# CX3_Camera.net
KiCad netlist of a schematic drawn in Altium Designer
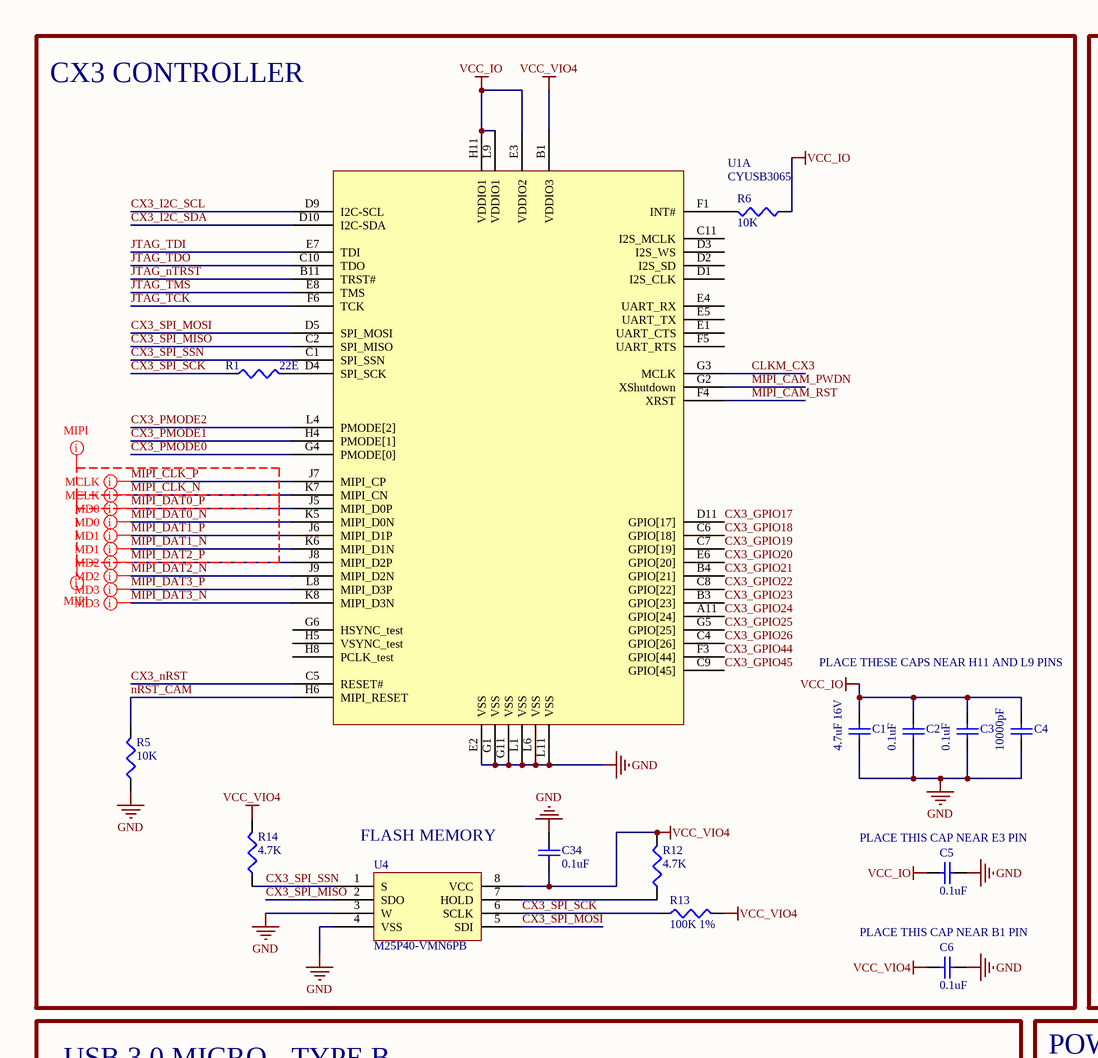
[diagram p0: CX3_Camera.SchDoc, top left]
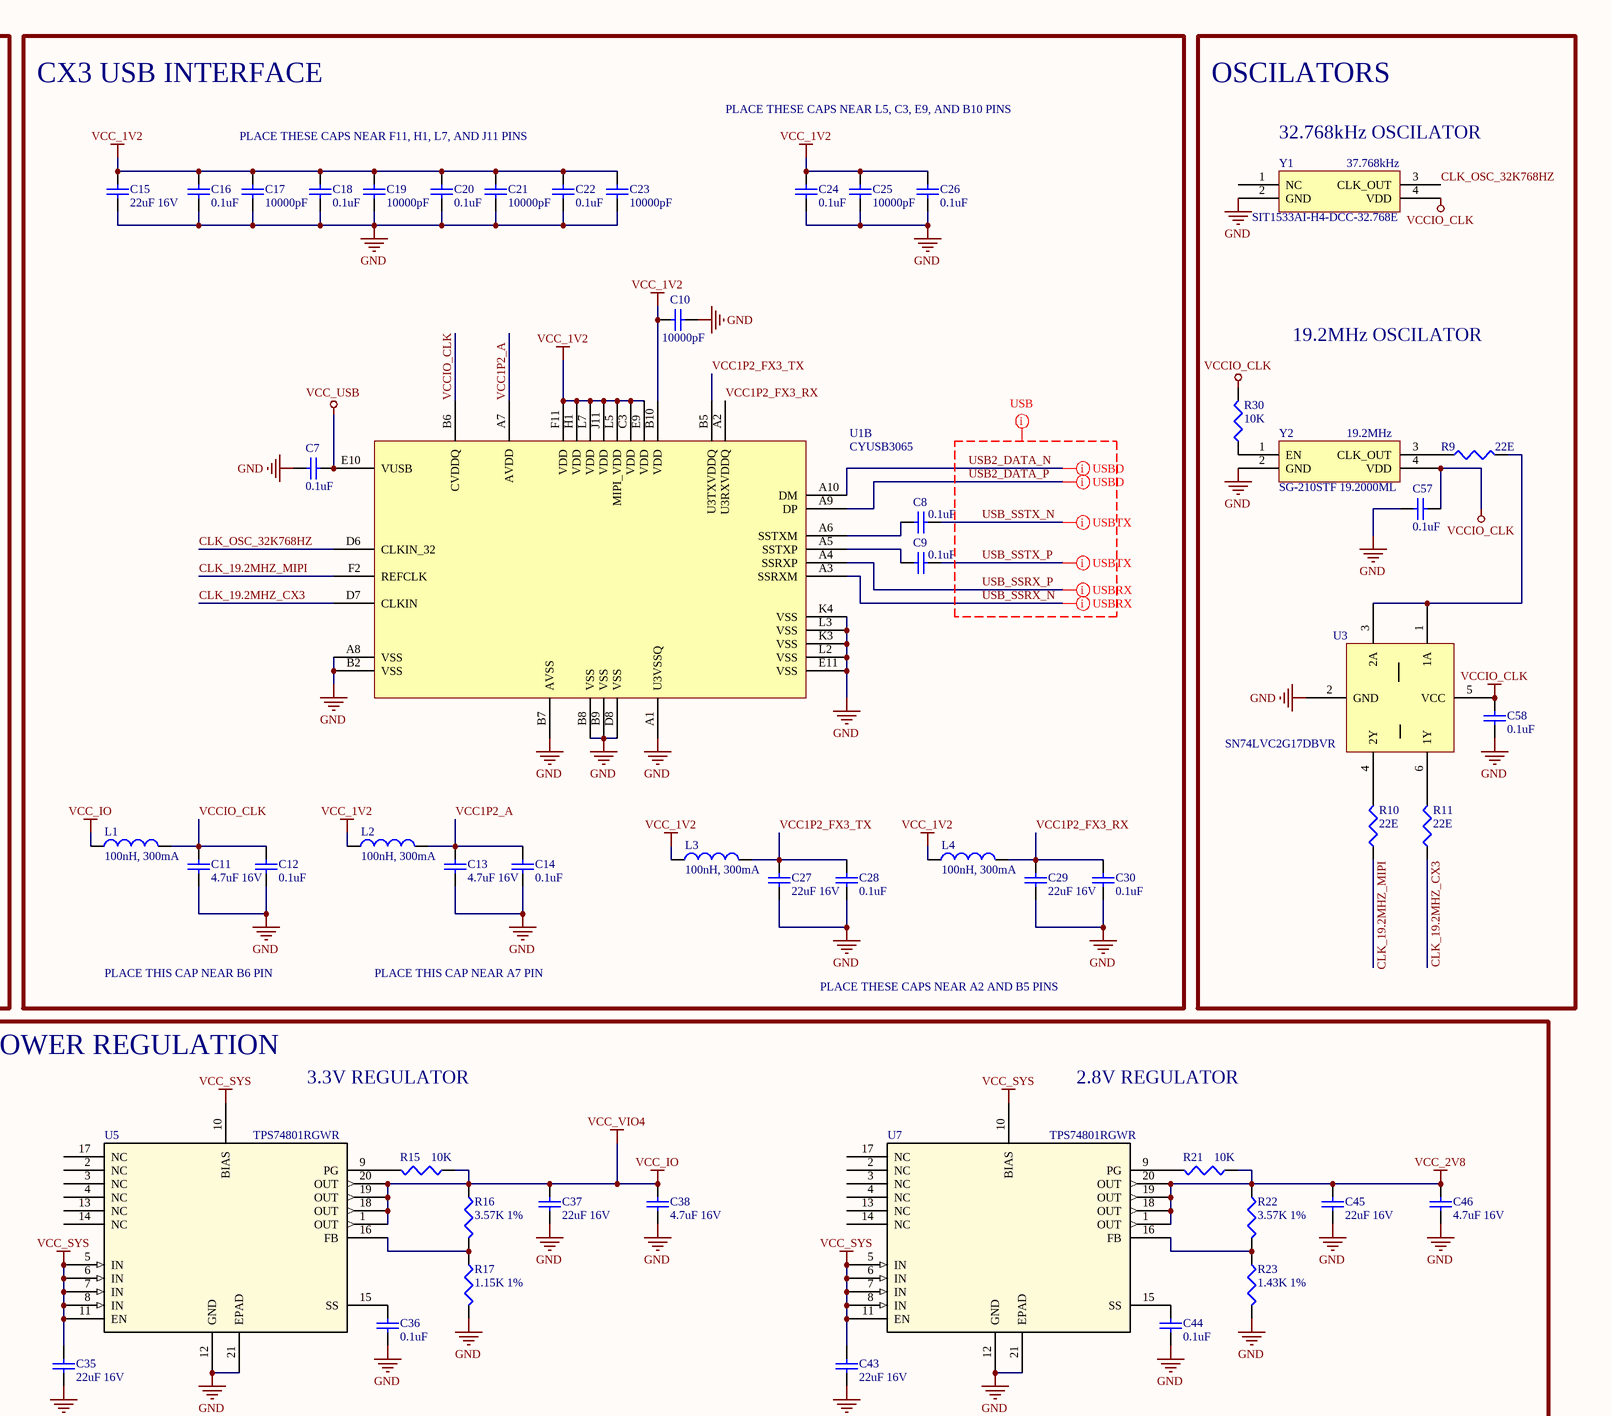
[diagram p1: CX3_Camera.SchDoc, top right]
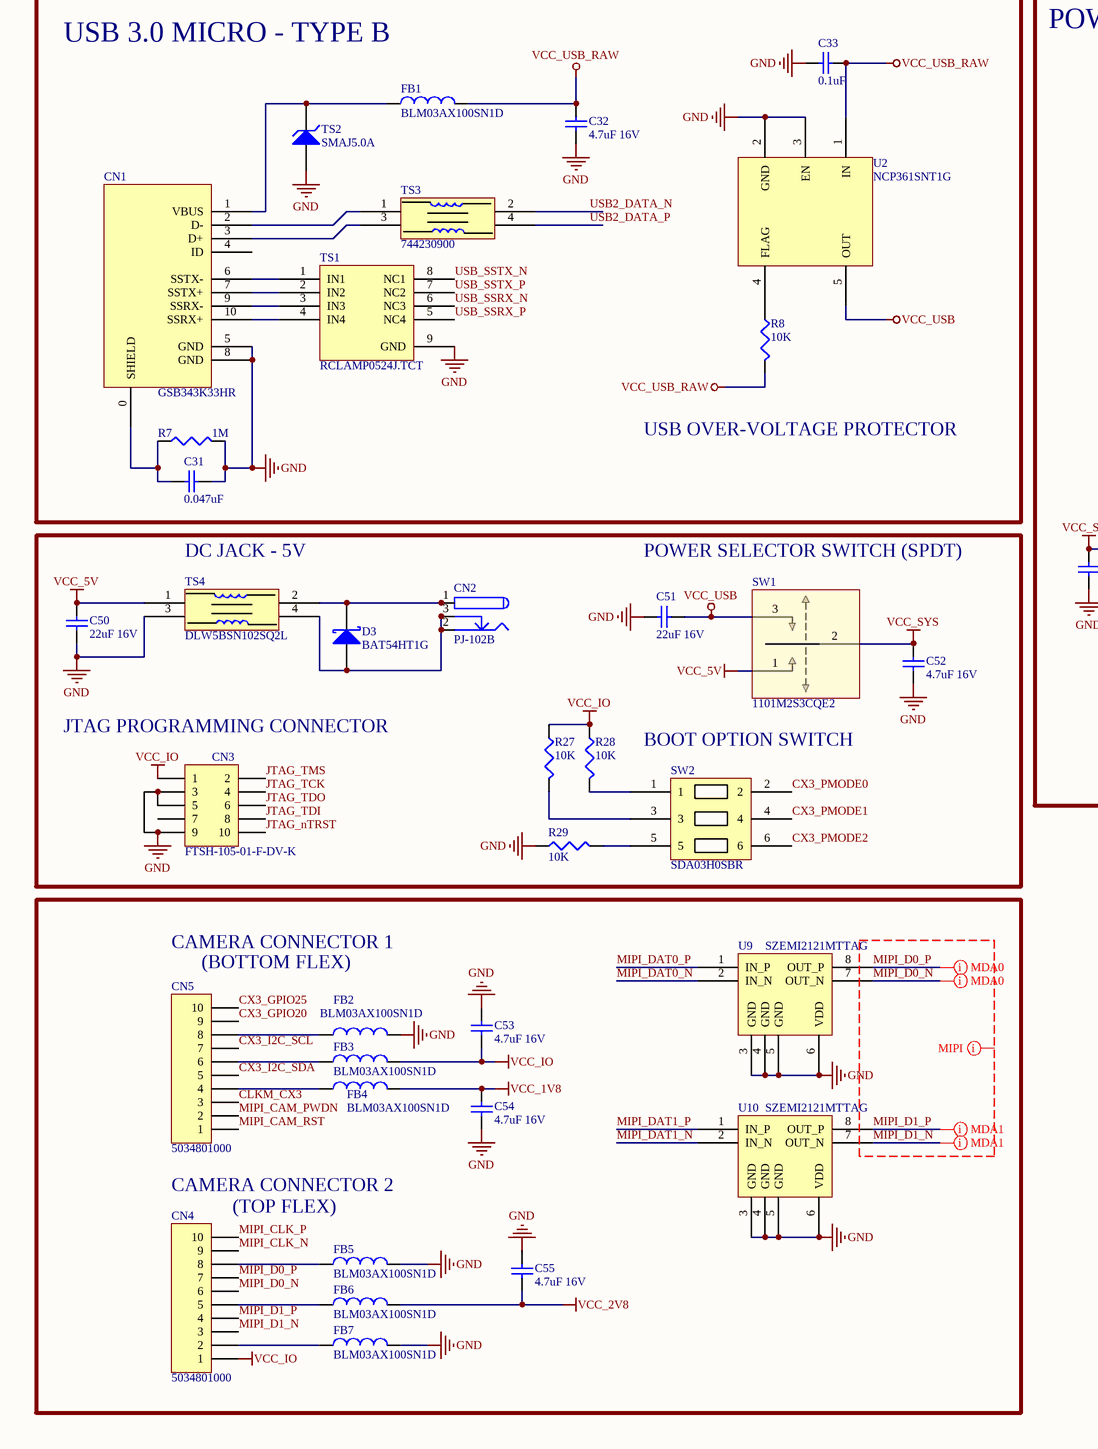
[diagram p2: CX3_Camera.SchDoc, bottom left]
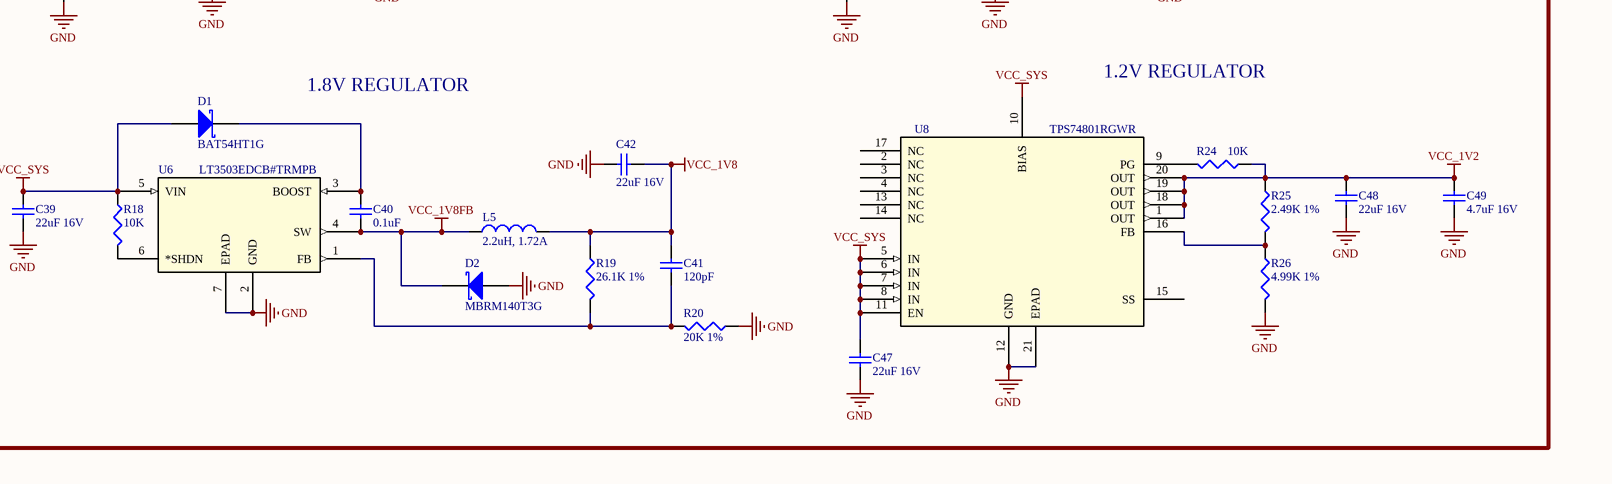
[diagram p3: CX3_Camera.SchDoc, bottom right]

(export (version "E")
  (design (tool "Eeschema 10.0.6"))
  (components
    (comp (ref "C1")
      (value "4.7uF 16V")
      (footprint "1608[0603]")
      (description "Capacitor (Semiconductor SIM Model)")
      (fields (field (name "PUBLISHER") "Altium Limited"))
      (libsource (lib "Miscellaneous Devices") (part "Cap Semi"))
    )
    (comp (ref "C2")
      (value "0.1uF")
      (footprint "0402")
      (description "Capacitor (Semiconductor SIM Model)")
      (fields (field (name "PUBLISHER") "Altium Limited"))
      (libsource (lib "Miscellaneous Devices") (part "Cap Semi"))
    )
    (comp (ref "C3")
      (value "0.1uF")
      (footprint "0402")
      (description "Capacitor (Semiconductor SIM Model)")
      (fields (field (name "PUBLISHER") "Altium Limited"))
      (libsource (lib "Miscellaneous Devices") (part "Cap Semi"))
    )
    (comp (ref "C4")
      (value "10000pF")
      (footprint "0402")
      (description "Capacitor (Semiconductor SIM Model)")
      (fields (field (name "PUBLISHER") "Altium Limited"))
      (libsource (lib "Miscellaneous Devices") (part "Cap Semi"))
    )
    (comp (ref "C5")
      (value "0.1uF")
      (footprint "0402")
      (description "Capacitor (Semiconductor SIM Model)")
      (fields (field (name "PUBLISHER") "Altium Limited"))
      (libsource (lib "Miscellaneous Devices") (part "Cap Semi"))
    )
    (comp (ref "C6")
      (value "0.1uF")
      (footprint "0402")
      (description "Capacitor (Semiconductor SIM Model)")
      (fields (field (name "PUBLISHER") "Altium Limited"))
      (libsource (lib "Miscellaneous Devices") (part "Cap Semi"))
    )
    (comp (ref "C7")
      (value "0.1uF")
      (footprint "0402")
      (description "Capacitor (Semiconductor SIM Model)")
      (fields (field (name "PUBLISHER") "Altium Limited"))
      (libsource (lib "Miscellaneous Devices") (part "Cap Semi"))
    )
    (comp (ref "C8")
      (value "0.1uF")
      (footprint "0402")
      (description "Capacitor (Semiconductor SIM Model)")
      (fields (field (name "PUBLISHER") "Altium Limited"))
      (libsource (lib "Miscellaneous Devices") (part "Cap Semi"))
    )
    (comp (ref "C9")
      (value "0.1uF")
      (footprint "0402")
      (description "Capacitor (Semiconductor SIM Model)")
      (fields (field (name "PUBLISHER") "Altium Limited"))
      (libsource (lib "Miscellaneous Devices") (part "Cap Semi"))
    )
    (comp (ref "C10")
      (value "10000pF")
      (footprint "0402")
      (description "Capacitor (Semiconductor SIM Model)")
      (fields (field (name "PUBLISHER") "Altium Limited"))
      (libsource (lib "Miscellaneous Devices") (part "Cap Semi"))
    )
    (comp (ref "C11")
      (value "4.7uF 16V")
      (footprint "1608[0603]")
      (description "Capacitor (Semiconductor SIM Model)")
      (fields (field (name "PUBLISHER") "Altium Limited"))
      (libsource (lib "Miscellaneous Devices") (part "Cap Semi"))
    )
    (comp (ref "C12")
      (value "0.1uF")
      (footprint "0402")
      (description "Capacitor (Semiconductor SIM Model)")
      (fields (field (name "PUBLISHER") "Altium Limited"))
      (libsource (lib "Miscellaneous Devices") (part "Cap Semi"))
    )
    (comp (ref "C13")
      (value "4.7uF 16V")
      (footprint "1608[0603]")
      (description "Capacitor (Semiconductor SIM Model)")
      (fields (field (name "PUBLISHER") "Altium Limited"))
      (libsource (lib "Miscellaneous Devices") (part "Cap Semi"))
    )
    (comp (ref "C14")
      (value "0.1uF")
      (footprint "0402")
      (description "Capacitor (Semiconductor SIM Model)")
      (fields (field (name "PUBLISHER") "Altium Limited"))
      (libsource (lib "Miscellaneous Devices") (part "Cap Semi"))
    )
    (comp (ref "C15")
      (value "22uF 16V")
      (footprint "C1206")
      (description "Capacitor (Semiconductor SIM Model)")
      (fields (field (name "PUBLISHER") "Altium Limited"))
      (libsource (lib "Miscellaneous Devices") (part "Cap Semi"))
    )
    (comp (ref "C16")
      (value "0.1uF")
      (footprint "0402")
      (description "Capacitor (Semiconductor SIM Model)")
      (fields (field (name "PUBLISHER") "Altium Limited"))
      (libsource (lib "Miscellaneous Devices") (part "Cap Semi"))
    )
    (comp (ref "C17")
      (value "10000pF")
      (footprint "0402")
      (description "Capacitor (Semiconductor SIM Model)")
      (fields (field (name "PUBLISHER") "Altium Limited"))
      (libsource (lib "Miscellaneous Devices") (part "Cap Semi"))
    )
    (comp (ref "C18")
      (value "0.1uF")
      (footprint "0402")
      (description "Capacitor (Semiconductor SIM Model)")
      (fields (field (name "PUBLISHER") "Altium Limited"))
      (libsource (lib "Miscellaneous Devices") (part "Cap Semi"))
    )
    (comp (ref "C19")
      (value "10000pF")
      (footprint "0402")
      (description "Capacitor (Semiconductor SIM Model)")
      (fields (field (name "PUBLISHER") "Altium Limited"))
      (libsource (lib "Miscellaneous Devices") (part "Cap Semi"))
    )
    (comp (ref "C20")
      (value "0.1uF")
      (footprint "0402")
      (description "Capacitor (Semiconductor SIM Model)")
      (fields (field (name "PUBLISHER") "Altium Limited"))
      (libsource (lib "Miscellaneous Devices") (part "Cap Semi"))
    )
    (comp (ref "C21")
      (value "10000pF")
      (footprint "0402")
      (description "Capacitor (Semiconductor SIM Model)")
      (fields (field (name "PUBLISHER") "Altium Limited"))
      (libsource (lib "Miscellaneous Devices") (part "Cap Semi"))
    )
    (comp (ref "C22")
      (value "0.1uF")
      (footprint "0402")
      (description "Capacitor (Semiconductor SIM Model)")
      (fields (field (name "PUBLISHER") "Altium Limited"))
      (libsource (lib "Miscellaneous Devices") (part "Cap Semi"))
    )
    (comp (ref "C23")
      (value "10000pF")
      (footprint "0402")
      (description "Capacitor (Semiconductor SIM Model)")
      (fields (field (name "PUBLISHER") "Altium Limited"))
      (libsource (lib "Miscellaneous Devices") (part "Cap Semi"))
    )
    (comp (ref "C24")
      (value "0.1uF")
      (footprint "0402")
      (description "Capacitor (Semiconductor SIM Model)")
      (fields (field (name "PUBLISHER") "Altium Limited"))
      (libsource (lib "Miscellaneous Devices") (part "Cap Semi"))
    )
    (comp (ref "C25")
      (value "10000pF")
      (footprint "0402")
      (description "Capacitor (Semiconductor SIM Model)")
      (fields (field (name "PUBLISHER") "Altium Limited"))
      (libsource (lib "Miscellaneous Devices") (part "Cap Semi"))
    )
    (comp (ref "C26")
      (value "0.1uF")
      (footprint "0402")
      (description "Capacitor (Semiconductor SIM Model)")
      (fields (field (name "PUBLISHER") "Altium Limited"))
      (libsource (lib "Miscellaneous Devices") (part "Cap Semi"))
    )
    (comp (ref "C27")
      (value "22uF 16V")
      (footprint "C1206")
      (description "Capacitor (Semiconductor SIM Model)")
      (fields (field (name "PUBLISHER") "Altium Limited"))
      (libsource (lib "Miscellaneous Devices") (part "Cap Semi"))
    )
    (comp (ref "C28")
      (value "0.1uF")
      (footprint "0402")
      (description "Capacitor (Semiconductor SIM Model)")
      (fields (field (name "PUBLISHER") "Altium Limited"))
      (libsource (lib "Miscellaneous Devices") (part "Cap Semi"))
    )
    (comp (ref "C29")
      (value "22uF 16V")
      (footprint "C1206")
      (description "Capacitor (Semiconductor SIM Model)")
      (fields (field (name "PUBLISHER") "Altium Limited"))
      (libsource (lib "Miscellaneous Devices") (part "Cap Semi"))
    )
    (comp (ref "C30")
      (value "0.1uF")
      (footprint "0402")
      (description "Capacitor (Semiconductor SIM Model)")
      (fields (field (name "PUBLISHER") "Altium Limited"))
      (libsource (lib "Miscellaneous Devices") (part "Cap Semi"))
    )
    (comp (ref "C31")
      (value "0.047uF")
      (footprint "C1210")
      (description "Capacitor (Semiconductor SIM Model)")
      (fields (field (name "PUBLISHER") "Altium Limited"))
      (libsource (lib "Miscellaneous Devices") (part "Cap Semi"))
    )
    (comp (ref "C32")
      (value "4.7uF 16V")
      (footprint "1608[0603]")
      (description "Capacitor (Semiconductor SIM Model)")
      (fields (field (name "PUBLISHER") "Altium Limited"))
      (libsource (lib "Miscellaneous Devices") (part "Cap Semi"))
    )
    (comp (ref "C33")
      (value "0.1uF")
      (footprint "0402")
      (description "Capacitor (Semiconductor SIM Model)")
      (fields (field (name "PUBLISHER") "Altium Limited"))
      (libsource (lib "Miscellaneous Devices") (part "Cap Semi"))
    )
    (comp (ref "C34")
      (value "0.1uF")
      (footprint "0402")
      (description "Capacitor (Semiconductor SIM Model)")
      (fields (field (name "PUBLISHER") "Altium Limited"))
      (libsource (lib "Miscellaneous Devices") (part "Cap Semi"))
    )
    (comp (ref "C35")
      (value "22uF 16V")
      (footprint "C1206")
      (description "Capacitor (Semiconductor SIM Model)")
      (fields (field (name "PUBLISHER") "Altium Limited"))
      (libsource (lib "Miscellaneous Devices") (part "Cap Semi"))
    )
    (comp (ref "C36")
      (value "0.1uF")
      (footprint "0402")
      (description "Capacitor (Semiconductor SIM Model)")
      (fields (field (name "PUBLISHER") "Altium Limited"))
      (libsource (lib "Miscellaneous Devices") (part "Cap Semi"))
    )
    (comp (ref "C37")
      (value "22uF 16V")
      (footprint "C1206")
      (description "Capacitor (Semiconductor SIM Model)")
      (fields (field (name "PUBLISHER") "Altium Limited"))
      (libsource (lib "Miscellaneous Devices") (part "Cap Semi"))
    )
    (comp (ref "C38")
      (value "4.7uF 16V")
      (footprint "1608[0603]")
      (description "Capacitor (Semiconductor SIM Model)")
      (fields (field (name "PUBLISHER") "Altium Limited"))
      (libsource (lib "Miscellaneous Devices") (part "Cap Semi"))
    )
    (comp (ref "C39")
      (value "22uF 16V")
      (footprint "C1206")
      (description "Capacitor (Semiconductor SIM Model)")
      (fields (field (name "PUBLISHER") "Altium Limited"))
      (libsource (lib "Miscellaneous Devices") (part "Cap Semi"))
    )
    (comp (ref "C40")
      (value "0.1uF")
      (footprint "0402")
      (description "Capacitor (Semiconductor SIM Model)")
      (fields (field (name "PUBLISHER") "Altium Limited"))
      (libsource (lib "Miscellaneous Devices") (part "Cap Semi"))
    )
    (comp (ref "C41")
      (value "120pF")
      (footprint "0402")
      (description "Capacitor (Semiconductor SIM Model)")
      (fields (field (name "PUBLISHER") "Altium Limited"))
      (libsource (lib "Miscellaneous Devices") (part "Cap Semi"))
    )
    (comp (ref "C42")
      (value "22uF 16V")
      (footprint "C1206")
      (description "Capacitor (Semiconductor SIM Model)")
      (fields (field (name "PUBLISHER") "Altium Limited"))
      (libsource (lib "Miscellaneous Devices") (part "Cap Semi"))
    )
    (comp (ref "C43")
      (value "22uF 16V")
      (footprint "C1206")
      (description "Capacitor (Semiconductor SIM Model)")
      (fields (field (name "PUBLISHER") "Altium Limited"))
      (libsource (lib "Miscellaneous Devices") (part "Cap Semi"))
    )
    (comp (ref "C44")
      (value "0.1uF")
      (footprint "0402")
      (description "Capacitor (Semiconductor SIM Model)")
      (fields (field (name "PUBLISHER") "Altium Limited"))
      (libsource (lib "Miscellaneous Devices") (part "Cap Semi"))
    )
    (comp (ref "C45")
      (value "22uF 16V")
      (footprint "C1206")
      (description "Capacitor (Semiconductor SIM Model)")
      (fields (field (name "PUBLISHER") "Altium Limited"))
      (libsource (lib "Miscellaneous Devices") (part "Cap Semi"))
    )
    (comp (ref "C46")
      (value "4.7uF 16V")
      (footprint "1608[0603]")
      (description "Capacitor (Semiconductor SIM Model)")
      (fields (field (name "PUBLISHER") "Altium Limited"))
      (libsource (lib "Miscellaneous Devices") (part "Cap Semi"))
    )
    (comp (ref "C47")
      (value "22uF 16V")
      (footprint "C1206")
      (description "Capacitor (Semiconductor SIM Model)")
      (fields (field (name "PUBLISHER") "Altium Limited"))
      (libsource (lib "Miscellaneous Devices") (part "Cap Semi"))
    )
    (comp (ref "C48")
      (value "22uF 16V")
      (footprint "C1206")
      (description "Capacitor (Semiconductor SIM Model)")
      (fields (field (name "PUBLISHER") "Altium Limited"))
      (libsource (lib "Miscellaneous Devices") (part "Cap Semi"))
    )
    (comp (ref "C49")
      (value "4.7uF 16V")
      (footprint "1608[0603]")
      (description "Capacitor (Semiconductor SIM Model)")
      (fields (field (name "PUBLISHER") "Altium Limited"))
      (libsource (lib "Miscellaneous Devices") (part "Cap Semi"))
    )
    (comp (ref "C50")
      (value "22uF 16V")
      (footprint "C1206")
      (description "Capacitor (Semiconductor SIM Model)")
      (fields (field (name "PUBLISHER") "Altium Limited"))
      (libsource (lib "Miscellaneous Devices") (part "Cap Semi"))
    )
    (comp (ref "C51")
      (value "22uF 16V")
      (footprint "C1206")
      (description "Capacitor (Semiconductor SIM Model)")
      (fields (field (name "PUBLISHER") "Altium Limited"))
      (libsource (lib "Miscellaneous Devices") (part "Cap Semi"))
    )
    (comp (ref "C52")
      (value "4.7uF 16V")
      (footprint "C0805")
      (description "Capacitor (Semiconductor SIM Model)")
      (fields (field (name "PUBLISHER") "Altium Limited"))
      (libsource (lib "Miscellaneous Devices") (part "Cap Semi"))
    )
    (comp (ref "C53")
      (value "4.7uF 16V")
      (footprint "1608[0603]")
      (description "Capacitor (Semiconductor SIM Model)")
      (fields (field (name "PUBLISHER") "Altium Limited"))
      (libsource (lib "Miscellaneous Devices") (part "Cap Semi"))
    )
    (comp (ref "C54")
      (value "4.7uF 16V")
      (footprint "1608[0603]")
      (description "Capacitor (Semiconductor SIM Model)")
      (fields (field (name "PUBLISHER") "Altium Limited"))
      (libsource (lib "Miscellaneous Devices") (part "Cap Semi"))
    )
    (comp (ref "C55")
      (value "4.7uF 16V")
      (footprint "1608[0603]")
      (description "Capacitor (Semiconductor SIM Model)")
      (fields (field (name "PUBLISHER") "Altium Limited"))
      (libsource (lib "Miscellaneous Devices") (part "Cap Semi"))
    )
    (comp (ref "C57")
      (value "0.1uF")
      (footprint "0402")
      (description "Capacitor (Semiconductor SIM Model)")
      (fields (field (name "PUBLISHER") "Altium Limited"))
      (libsource (lib "Miscellaneous Devices") (part "Cap Semi"))
    )
    (comp (ref "C58")
      (value "0.1uF")
      (footprint "0402")
      (description "Capacitor (Semiconductor SIM Model)")
      (fields (field (name "PUBLISHER") "Altium Limited"))
      (libsource (lib "Miscellaneous Devices") (part "Cap Semi"))
    )
    (comp (ref "CN1")
      (value "GSB343K33HR")
      (footprint "USB3MicroB")
      (libsource (lib "CX3_Camera") (part "GSB343K33HR"))
    )
    (comp (ref "CN2")
      (value "PJ-102B")
      (footprint "PJ-102B")
      (description "Low Voltage Power Supply Connector")
      (fields (field (name "PUBLISHER") "Altium Limited"))
      (libsource (lib "Miscellaneous Connectors") (part "PWR2.5"))
    )
    (comp (ref "CN3")
      (value "FTSH-105-01-F-DV-K")
      (footprint "FTSH-105-01-F-DV-K")
      (description "Header, 5-Pin, Dual row")
      (fields (field (name "PUBLISHER") "Altium Limited"))
      (libsource (lib "Miscellaneous Connectors") (part "MHDR2X5"))
    )
    (comp (ref "CN4")
      (value "5034801000")
      (footprint "5034801000")
      (description "Header, 10-Pin")
      (fields (field (name "PUBLISHER") "Altium Limited"))
      (libsource (lib "Miscellaneous Connectors") (part "Header 10"))
    )
    (comp (ref "CN5")
      (value "5034801000")
      (footprint "5034801000")
      (description "Header, 10-Pin")
      (fields (field (name "PUBLISHER") "Altium Limited"))
      (libsource (lib "Miscellaneous Connectors") (part "Header 10"))
    )
    (comp (ref "D1")
      (value "BAT54HT1G")
      (footprint "SOD-323")
      (description "Silicon AF Schottky Rectifier Diode")
      (fields (field (name "PUBLISHER") "Altium Limited"))
      (libsource (lib "Infineon Discrete Diode") (part "BAT60B"))
    )
    (comp (ref "D2")
      (value "MBRM140T3G")
      (footprint "DO-216AA")
      (description "Silicon AF Schottky Rectifier Diode")
      (fields (field (name "PUBLISHER") "Altium Limited"))
      (libsource (lib "Infineon Discrete Diode") (part "BAT60B"))
    )
    (comp (ref "D3")
      (value "BAT54HT1G")
      (footprint "DO-214AC")
      (description "Silicon AF Schottky Rectifier Diode")
      (fields (field (name "PUBLISHER") "Altium Limited"))
      (libsource (lib "Infineon Discrete Diode") (part "BAT60B"))
    )
    (comp (ref "FB1")
      (value "BLM03AX100SN1D")
      (footprint "1608[0603]")
      (description "Inductor")
      (fields (field (name "PUBLISHER") "Altium Limited"))
      (libsource (lib "Miscellaneous Devices") (part "Inductor"))
    )
    (comp (ref "FB2")
      (value "BLM03AX100SN1D")
      (footprint "INDC1608L")
      (description "Inductor")
      (fields (field (name "PUBLISHER") "Altium Limited"))
      (libsource (lib "Miscellaneous Devices") (part "Inductor"))
    )
    (comp (ref "FB3")
      (value "BLM03AX100SN1D")
      (footprint "INDC1608L")
      (description "Inductor")
      (fields (field (name "PUBLISHER") "Altium Limited"))
      (libsource (lib "Miscellaneous Devices") (part "Inductor"))
    )
    (comp (ref "FB4")
      (value "BLM03AX100SN1D")
      (footprint "INDC1608L")
      (description "Inductor")
      (fields (field (name "PUBLISHER") "Altium Limited"))
      (libsource (lib "Miscellaneous Devices") (part "Inductor"))
    )
    (comp (ref "FB5")
      (value "BLM03AX100SN1D")
      (footprint "INDC1608L")
      (description "Inductor")
      (fields (field (name "PUBLISHER") "Altium Limited"))
      (libsource (lib "Miscellaneous Devices") (part "Inductor"))
    )
    (comp (ref "FB6")
      (value "BLM03AX100SN1D")
      (footprint "INDC1608L")
      (description "Inductor")
      (fields (field (name "PUBLISHER") "Altium Limited"))
      (libsource (lib "Miscellaneous Devices") (part "Inductor"))
    )
    (comp (ref "FB7")
      (value "BLM03AX100SN1D")
      (footprint "INDC1608L")
      (description "Inductor")
      (fields (field (name "PUBLISHER") "Altium Limited"))
      (libsource (lib "Miscellaneous Devices") (part "Inductor"))
    )
    (comp (ref "L1")
      (value "100nH, 300mA")
      (footprint "INDC1608L")
      (description "Inductor")
      (fields (field (name "PUBLISHER") "Altium Limited"))
      (libsource (lib "Miscellaneous Devices") (part "Inductor"))
    )
    (comp (ref "L2")
      (value "100nH, 300mA")
      (footprint "INDC1608L")
      (description "Inductor")
      (fields (field (name "PUBLISHER") "Altium Limited"))
      (libsource (lib "Miscellaneous Devices") (part "Inductor"))
    )
    (comp (ref "L3")
      (value "100nH, 300mA")
      (footprint "INDC1608L")
      (description "Inductor")
      (fields (field (name "PUBLISHER") "Altium Limited"))
      (libsource (lib "Miscellaneous Devices") (part "Inductor"))
    )
    (comp (ref "L4")
      (value "100nH, 300mA")
      (footprint "INDC1608L")
      (description "Inductor")
      (fields (field (name "PUBLISHER") "Altium Limited"))
      (libsource (lib "Miscellaneous Devices") (part "Inductor"))
    )
    (comp (ref "L5")
      (value "2.2uH, 1.72A")
      (footprint "6-0805_N")
      (description "Inductor")
      (fields (field (name "PUBLISHER") "Altium Limited"))
      (libsource (lib "Miscellaneous Devices") (part "Inductor"))
    )
    (comp (ref "R1")
      (value "22E")
      (footprint "0402")
      (description "Resistor")
      (fields (field (name "PUBLISHER") "Altium Limited"))
      (libsource (lib "Miscellaneous Devices") (part "Res3"))
    )
    (comp (ref "R5")
      (value "10K")
      (footprint "0402")
      (description "Resistor")
      (fields (field (name "PUBLISHER") "Altium Limited"))
      (libsource (lib "Miscellaneous Devices") (part "Res3"))
    )
    (comp (ref "R6")
      (value "10K")
      (footprint "0402")
      (description "Resistor")
      (fields (field (name "PUBLISHER") "Altium Limited"))
      (libsource (lib "Miscellaneous Devices") (part "Res3"))
    )
    (comp (ref "R7")
      (value "1M")
      (footprint "0402")
      (description "Resistor")
      (fields (field (name "PUBLISHER") "Altium Limited"))
      (libsource (lib "Miscellaneous Devices") (part "Res3"))
    )
    (comp (ref "R8")
      (value "10K")
      (footprint "0402")
      (description "Resistor")
      (fields (field (name "PUBLISHER") "Altium Limited"))
      (libsource (lib "Miscellaneous Devices") (part "Res3"))
    )
    (comp (ref "R9")
      (value "22E")
      (footprint "J1-0603")
      (description "Resistor")
      (fields (field (name "PUBLISHER") "Altium Limited"))
      (libsource (lib "Miscellaneous Devices") (part "Res3"))
    )
    (comp (ref "R10")
      (value "22E")
      (footprint "0402")
      (description "Resistor")
      (fields (field (name "PUBLISHER") "Altium Limited"))
      (libsource (lib "Miscellaneous Devices") (part "Res3"))
    )
    (comp (ref "R11")
      (value "22E")
      (footprint "0402")
      (description "Resistor")
      (fields (field (name "PUBLISHER") "Altium Limited"))
      (libsource (lib "Miscellaneous Devices") (part "Res3"))
    )
    (comp (ref "R12")
      (value "4.7K")
      (footprint "0402")
      (description "Resistor")
      (fields (field (name "PUBLISHER") "Altium Limited"))
      (libsource (lib "Miscellaneous Devices") (part "Res3"))
    )
    (comp (ref "R13")
      (value "100K 1%")
      (footprint "0402")
      (description "Resistor")
      (fields (field (name "PUBLISHER") "Altium Limited"))
      (libsource (lib "Miscellaneous Devices") (part "Res3"))
    )
    (comp (ref "R14")
      (value "4.7K")
      (footprint "0402")
      (description "Resistor")
      (fields (field (name "PUBLISHER") "Altium Limited"))
      (libsource (lib "Miscellaneous Devices") (part "Res3"))
    )
    (comp (ref "R15")
      (value "10K")
      (footprint "0402")
      (description "Resistor")
      (fields (field (name "PUBLISHER") "Altium Limited"))
      (libsource (lib "Miscellaneous Devices") (part "Res3"))
    )
    (comp (ref "R16")
      (value "3.57K 1%")
      (footprint "0402")
      (description "Resistor")
      (fields (field (name "PUBLISHER") "Altium Limited"))
      (libsource (lib "Miscellaneous Devices") (part "Res3"))
    )
    (comp (ref "R17")
      (value "1.15K 1%")
      (footprint "0402")
      (description "Resistor")
      (fields (field (name "PUBLISHER") "Altium Limited"))
      (libsource (lib "Miscellaneous Devices") (part "Res3"))
    )
    (comp (ref "R18")
      (value "10K")
      (footprint "0402")
      (description "Resistor")
      (fields (field (name "PUBLISHER") "Altium Limited"))
      (libsource (lib "Miscellaneous Devices") (part "Res3"))
    )
    (comp (ref "R19")
      (value "26.1K 1%")
      (footprint "0402")
      (description "Resistor")
      (fields (field (name "PUBLISHER") "Altium Limited"))
      (libsource (lib "Miscellaneous Devices") (part "Res3"))
    )
    (comp (ref "R20")
      (value "20K 1%")
      (footprint "0402")
      (description "Resistor")
      (fields (field (name "PUBLISHER") "Altium Limited"))
      (libsource (lib "Miscellaneous Devices") (part "Res3"))
    )
    (comp (ref "R21")
      (value "10K")
      (footprint "0402")
      (description "Resistor")
      (fields (field (name "PUBLISHER") "Altium Limited"))
      (libsource (lib "Miscellaneous Devices") (part "Res3"))
    )
    (comp (ref "R22")
      (value "3.57K 1%")
      (footprint "0402")
      (description "Resistor")
      (fields (field (name "PUBLISHER") "Altium Limited"))
      (libsource (lib "Miscellaneous Devices") (part "Res3"))
    )
    (comp (ref "R23")
      (value "1.43K 1%")
      (footprint "0402")
      (description "Resistor")
      (fields (field (name "PUBLISHER") "Altium Limited"))
      (libsource (lib "Miscellaneous Devices") (part "Res3"))
    )
    (comp (ref "R24")
      (value "10K")
      (footprint "0402")
      (description "Resistor")
      (fields (field (name "PUBLISHER") "Altium Limited"))
      (libsource (lib "Miscellaneous Devices") (part "Res3"))
    )
    (comp (ref "R25")
      (value "2.49K 1%")
      (footprint "0402")
      (description "Resistor")
      (fields (field (name "PUBLISHER") "Altium Limited"))
      (libsource (lib "Miscellaneous Devices") (part "Res3"))
    )
    (comp (ref "R26")
      (value "4.99K 1%")
      (footprint "0402")
      (description "Resistor")
      (fields (field (name "PUBLISHER") "Altium Limited"))
      (libsource (lib "Miscellaneous Devices") (part "Res3"))
    )
    (comp (ref "R27")
      (value "10K")
      (footprint "0402")
      (description "Resistor")
      (fields (field (name "PUBLISHER") "Altium Limited"))
      (libsource (lib "Miscellaneous Devices") (part "Res3"))
    )
    (comp (ref "R28")
      (value "10K")
      (footprint "0402")
      (description "Resistor")
      (fields (field (name "PUBLISHER") "Altium Limited"))
      (libsource (lib "Miscellaneous Devices") (part "Res3"))
    )
    (comp (ref "R29")
      (value "10K")
      (footprint "0402")
      (description "Resistor")
      (fields (field (name "PUBLISHER") "Altium Limited"))
      (libsource (lib "Miscellaneous Devices") (part "Res3"))
    )
    (comp (ref "R30")
      (value "10K")
      (footprint "0402")
      (description "Resistor")
      (fields (field (name "PUBLISHER") "Altium Limited"))
      (libsource (lib "Miscellaneous Devices") (part "Res3"))
    )
    (comp (ref "SW1")
      (value "1101M2S3CQE2")
      (footprint "1101M2S3CQE2")
      (description "Imported")
      (fields (field (name "COPYRIGHT") "Copyright (C) 2015 Accelerated Designs. All rights reserved"))
      (libsource (lib "CX3_Camera") (part "1101M2S3CQE2"))
    )
    (comp (ref "SW2")
      (value "SDA03H0SBR")
      (footprint "SDA03H0SBR")
      (libsource (lib "CX3_Camera") (part "SDA03H0SBR"))
    )
    (comp (ref "TS1")
      (value "RCLAMP0524J.TCT")
      (footprint "RCLAMP0524J")
      (libsource (lib "CX3_Camera") (part "RCLAMP0524J"))
    )
    (comp (ref "TS2")
      (value "SMAJ5.0A")
      (footprint "DO-214AC")
      (description "Silicon Zener Diode")
      (fields (field (name "PUBLISHER") "Altium Limited"))
      (libsource (lib "Vishay Lite-On Discrete Diode") (part "DL5243B"))
    )
    (comp (ref "TS3") (value "744230900") (libsource (lib "CX3_Camera") (part "CHOKE_COM")))
    (comp (ref "TS4")
      (value "DLW5BSN102SQ2L")
      (footprint "SRF0504-102Y")
      (libsource (lib "CX3_Camera") (part "CHOKE_COM"))
    )
    (comp (ref "U1")
      (value "CYUSB3065")
      (description "Cypress CX3")
      (libsource (lib "CX3_Camera") (part "CYUSB3065"))
    )
    (comp (ref "U2")
      (value "NCP361SNT1G")
      (footprint "SOT-23-5")
      (libsource (lib "CX3_Camera") (part "NCP361SNT1G"))
    )
    (comp (ref "U3")
      (value "SN74LVC2G17DBVR")
      (footprint "SOT-23_A_N")
      (libsource (lib "CX3_Camera") (part "SN74LVC2G17DBVR"))
    )
    (comp (ref "U4")
      (value "M25P40-VMN6PB")
      (footprint "SO8_M")
      (libsource (lib "CX3_Camera") (part "M25P40"))
    )
    (comp (ref "U5")
      (value "TPS74801RGWR")
      (footprint "RGW20_3P15X3P15")
      (description "Imported")
      (fields
        (field (name "GENERIC_PART_NUMBER") "TPS74801")
        (field (name "MANUFACTURER") "Texas Instruments")
        (field (name "COPYRIGHT") "Copyright (C) 2015 Accelerated Designs. All rights reserved")
      )
      (libsource (lib "CX3_Camera") (part "TPS74801RGWR"))
    )
    (comp (ref "U6")
      (value "LT3503EDCB#TRMPB")
      (footprint "DFN-6_DCB")
      (description "Imported")
      (fields
        (field (name "MANUFACTURER_PART_NUMBER") "lt3503edcb#trmpbf")
        (field (name "COPYRIGHT") "Copyright (C) 2016 Accelerated Designs. All rights reserved")
      )
      (libsource (lib "CX3_Camera") (part "LT3503EDCB#TRMPB"))
    )
    (comp (ref "U7")
      (value "TPS74801RGWR")
      (footprint "RGW20_3P15X3P15")
      (description "Imported")
      (fields
        (field (name "GENERIC_PART_NUMBER") "TPS74801")
        (field (name "MANUFACTURER") "Texas Instruments")
        (field (name "COPYRIGHT") "Copyright (C) 2015 Accelerated Designs. All rights reserved")
      )
      (libsource (lib "CX3_Camera") (part "TPS74801RGWR"))
    )
    (comp (ref "U8")
      (value "TPS74801RGWR")
      (footprint "RGW20_3P15X3P15")
      (description "Imported")
      (fields
        (field (name "GENERIC_PART_NUMBER") "TPS74801")
        (field (name "MANUFACTURER") "Texas Instruments")
        (field (name "COPYRIGHT") "Copyright (C) 2015 Accelerated Designs. All rights reserved")
      )
      (libsource (lib "CX3_Camera") (part "TPS74801RGWR"))
    )
    (comp (ref "U9")
      (value "SZEMI2121MTTAG")
      (footprint "SZEMI2121MTTAG")
      (libsource (lib "CX3_Camera") (part "SZEMI2121MTTAG"))
    )
    (comp (ref "U10")
      (value "SZEMI2121MTTAG")
      (footprint "SZEMI2121MTTAG")
      (libsource (lib "CX3_Camera") (part "SZEMI2121MTTAG"))
    )
    (comp (ref "Y1")
      (value "SIT1533AI-H4-DCC-32.768E")
      (footprint "SiT1533")
      (fields (field (name "ALTIUM_VALUE") "37.768kHz"))
      (libsource (lib "CX3_Camera") (part "OSCILATOR_32kHz"))
    )
    (comp (ref "Y2")
      (value "SG-210STF 19.2000ML")
      (footprint "SG5032")
      (fields (field (name "ALTIUM_VALUE") "19.2MHz"))
      (libsource (lib "CX3_Camera") (part "OSCILLATOR"))
    )
  )
  (nets
    (net (code "1") (name "/CLKM_CX3") (class "Default")
      (node (ref "CN5") (pin "3") (pinfunction "3_3") (pintype "passive"))
      (node (ref "U1") (pin "G3") (pinfunction "MCLK_G3") (pintype "passive"))
    )
    (net (code "2") (name "/CLK_19.2MHZ_CX3") (class "Default")
      (node (ref "R11") (pin "1") (pinfunction "1_1") (pintype "passive"))
      (node (ref "U1") (pin "D7") (pinfunction "CLKIN_D7") (pintype "passive"))
    )
    (net (code "3") (name "/CLK_19.2MHZ_MIPI") (class "Default")
      (node (ref "R10") (pin "1") (pinfunction "1_1") (pintype "passive"))
      (node (ref "U1") (pin "F2") (pinfunction "REFCLK_F2") (pintype "passive"))
    )
    (net (code "4") (name "/CLK_OSC_32K768HZ") (class "Default")
      (node (ref "U1") (pin "D6") (pinfunction "CLKIN_32_D6") (pintype "passive"))
      (node (ref "Y1") (pin "3") (pinfunction "CLK_OUT_3") (pintype "passive"))
    )
    (net (code "5") (name "/CX3_GPIO17") (class "Default")
      (node (ref "U1") (pin "D11") (pinfunction "GPIO[17]_D11") (pintype "passive"))
    )
    (net (code "6") (name "/CX3_GPIO18") (class "Default")
      (node (ref "U1") (pin "C6") (pinfunction "GPIO[18]_C6") (pintype "passive"))
    )
    (net (code "7") (name "/CX3_GPIO19") (class "Default")
      (node (ref "U1") (pin "C7") (pinfunction "GPIO[19]_C7") (pintype "passive"))
    )
    (net (code "8") (name "/CX3_GPIO20") (class "Default")
      (node (ref "CN5") (pin "9") (pinfunction "9_9") (pintype "passive"))
      (node (ref "U1") (pin "E6") (pinfunction "GPIO[20]_E6") (pintype "passive"))
    )
    (net (code "9") (name "/CX3_GPIO21") (class "Default")
      (node (ref "U1") (pin "B4") (pinfunction "GPIO[21]_B4") (pintype "passive"))
    )
    (net (code "10") (name "/CX3_GPIO22") (class "Default")
      (node (ref "U1") (pin "C8") (pinfunction "GPIO[22]_C8") (pintype "passive"))
    )
    (net (code "11") (name "/CX3_GPIO23") (class "Default")
      (node (ref "U1") (pin "B3") (pinfunction "GPIO[23]_B3") (pintype "passive"))
    )
    (net (code "12") (name "/CX3_GPIO24") (class "Default")
      (node (ref "U1") (pin "A11") (pinfunction "GPIO[24]_A11") (pintype "passive"))
    )
    (net (code "13") (name "/CX3_GPIO25") (class "Default")
      (node (ref "CN5") (pin "10") (pinfunction "10_10") (pintype "passive"))
      (node (ref "U1") (pin "G5") (pinfunction "GPIO[25]_G5") (pintype "passive"))
    )
    (net (code "14") (name "/CX3_GPIO26") (class "Default")
      (node (ref "U1") (pin "C4") (pinfunction "GPIO[26]_C4") (pintype "passive"))
    )
    (net (code "15") (name "/CX3_GPIO44") (class "Default")
      (node (ref "U1") (pin "F3") (pinfunction "GPIO[44]_F3") (pintype "passive"))
    )
    (net (code "16") (name "/CX3_GPIO45") (class "Default")
      (node (ref "U1") (pin "C9") (pinfunction "GPIO[45]_C9") (pintype "passive"))
    )
    (net (code "17") (name "/CX3_I2C_SCL") (class "Default")
      (node (ref "CN5") (pin "7") (pinfunction "7_7") (pintype "passive"))
      (node (ref "U1") (pin "D9") (pinfunction "I2C-SCL_D9") (pintype "passive"))
    )
    (net (code "18") (name "/CX3_I2C_SDA") (class "Default")
      (node (ref "CN5") (pin "5") (pinfunction "5_5") (pintype "passive"))
      (node (ref "U1") (pin "D10") (pinfunction "I2C-SDA_D10") (pintype "passive"))
    )
    (net (code "19") (name "/CX3_PMODE0") (class "Default")
      (node (ref "SW2") (pin "2") (pinfunction "2_2") (pintype "passive"))
      (node (ref "U1") (pin "G4") (pinfunction "PMODE[0]_G4") (pintype "passive"))
    )
    (net (code "20") (name "/CX3_PMODE1") (class "Default")
      (node (ref "SW2") (pin "4") (pinfunction "4_4") (pintype "passive"))
      (node (ref "U1") (pin "H4") (pinfunction "PMODE[1]_H4") (pintype "passive"))
    )
    (net (code "21") (name "/CX3_PMODE2") (class "Default")
      (node (ref "SW2") (pin "6") (pinfunction "6_6") (pintype "passive"))
      (node (ref "U1") (pin "L4") (pinfunction "PMODE[2]_L4") (pintype "passive"))
    )
    (net (code "22") (name "/CX3_SPI_MISO") (class "Default")
      (node (ref "U1") (pin "C2") (pinfunction "SPI_MISO_C2") (pintype "passive"))
      (node (ref "U4") (pin "2") (pinfunction "SDO_2") (pintype "passive"))
    )
    (net (code "23") (name "/CX3_SPI_MOSI") (class "Default")
      (node (ref "U1") (pin "D5") (pinfunction "SPI_MOSI_D5") (pintype "passive"))
      (node (ref "U4") (pin "5") (pinfunction "SDI_5") (pintype "passive"))
    )
    (net (code "24") (name "/CX3_SPI_SCK") (class "Default")
      (node (ref "R1") (pin "1") (pinfunction "1_1") (pintype "passive"))
      (node (ref "R13") (pin "1") (pinfunction "1_1") (pintype "passive"))
      (node (ref "U4") (pin "6") (pinfunction "SCLK_6") (pintype "passive"))
    )
    (net (code "25") (name "/CX3_SPI_SSN") (class "Default")
      (node (ref "R14") (pin "1") (pinfunction "1_1") (pintype "passive"))
      (node (ref "U1") (pin "C1") (pinfunction "SPI_SSN_C1") (pintype "passive"))
      (node (ref "U4") (pin "1") (pinfunction "S_1") (pintype "passive"))
    )
    (net (code "26") (name "/CX3_nRST") (class "Default")
      (node (ref "U1") (pin "C5") (pinfunction "RESET#_C5") (pintype "passive"))
    )
    (net (code "27") (name "/JTAG_TCK") (class "Default")
      (node (ref "CN3") (pin "4") (pinfunction "4_4") (pintype "passive"))
      (node (ref "U1") (pin "F6") (pinfunction "TCK_F6") (pintype "passive"))
    )
    (net (code "28") (name "/JTAG_TDI") (class "Default")
      (node (ref "CN3") (pin "8") (pinfunction "8_8") (pintype "passive"))
      (node (ref "U1") (pin "E7") (pinfunction "TDI_E7") (pintype "passive"))
    )
    (net (code "29") (name "/JTAG_TDO") (class "Default")
      (node (ref "CN3") (pin "6") (pinfunction "6_6") (pintype "passive"))
      (node (ref "U1") (pin "C10") (pinfunction "TDO_C10") (pintype "passive"))
    )
    (net (code "30") (name "/JTAG_TMS") (class "Default")
      (node (ref "CN3") (pin "2") (pinfunction "2_2") (pintype "passive"))
      (node (ref "U1") (pin "E8") (pinfunction "TMS_E8") (pintype "passive"))
    )
    (net (code "31") (name "/JTAG_nTRST") (class "Default")
      (node (ref "CN3") (pin "10") (pinfunction "10_10") (pintype "passive"))
      (node (ref "U1") (pin "B11") (pinfunction "TRST#_B11") (pintype "passive"))
    )
    (net (code "32") (name "/MIPI_CAM_PWDN") (class "Default")
      (node (ref "CN5") (pin "2") (pinfunction "2_2") (pintype "passive"))
      (node (ref "U1") (pin "G2") (pinfunction "XShutdown_G2") (pintype "passive"))
    )
    (net (code "33") (name "/MIPI_CAM_RST") (class "Default")
      (node (ref "CN5") (pin "1") (pinfunction "1_1") (pintype "passive"))
      (node (ref "U1") (pin "F4") (pinfunction "XRST_F4") (pintype "passive"))
    )
    (net (code "34") (name "/MIPI_CLK_N") (class "Default")
      (node (ref "CN4") (pin "9") (pinfunction "9_9") (pintype "passive"))
      (node (ref "U1") (pin "K7") (pinfunction "MIPI_CN_K7") (pintype "passive"))
    )
    (net (code "35") (name "/MIPI_CLK_P") (class "Default")
      (node (ref "CN4") (pin "10") (pinfunction "10_10") (pintype "passive"))
      (node (ref "U1") (pin "J7") (pinfunction "MIPI_CP_J7") (pintype "passive"))
    )
    (net (code "36") (name "/MIPI_D0_N") (class "Default")
      (node (ref "CN4") (pin "6") (pinfunction "6_6") (pintype "passive"))
      (node (ref "U9") (pin "7") (pinfunction "OUT_N_7") (pintype "passive"))
    )
    (net (code "37") (name "/MIPI_D0_P") (class "Default")
      (node (ref "CN4") (pin "7") (pinfunction "7_7") (pintype "passive"))
      (node (ref "U9") (pin "8") (pinfunction "OUT_P_8") (pintype "passive"))
    )
    (net (code "38") (name "/MIPI_D1_N") (class "Default")
      (node (ref "CN4") (pin "3") (pinfunction "3_3") (pintype "passive"))
      (node (ref "U10") (pin "7") (pinfunction "OUT_N_7") (pintype "passive"))
    )
    (net (code "39") (name "/MIPI_D1_P") (class "Default")
      (node (ref "CN4") (pin "4") (pinfunction "4_4") (pintype "passive"))
      (node (ref "U10") (pin "8") (pinfunction "OUT_P_8") (pintype "passive"))
    )
    (net (code "40") (name "/MIPI_DAT0_N") (class "Default")
      (node (ref "U1") (pin "K5") (pinfunction "MIPI_D0N_K5") (pintype "passive"))
      (node (ref "U9") (pin "2") (pinfunction "IN_N_2") (pintype "passive"))
    )
    (net (code "41") (name "/MIPI_DAT0_P") (class "Default")
      (node (ref "U1") (pin "J5") (pinfunction "MIPI_D0P_J5") (pintype "passive"))
      (node (ref "U9") (pin "1") (pinfunction "IN_P_1") (pintype "passive"))
    )
    (net (code "42") (name "/MIPI_DAT1_N") (class "Default")
      (node (ref "U1") (pin "K6") (pinfunction "MIPI_D1N_K6") (pintype "passive"))
      (node (ref "U10") (pin "2") (pinfunction "IN_N_2") (pintype "passive"))
    )
    (net (code "43") (name "/MIPI_DAT1_P") (class "Default")
      (node (ref "U1") (pin "J6") (pinfunction "MIPI_D1P_J6") (pintype "passive"))
      (node (ref "U10") (pin "1") (pinfunction "IN_P_1") (pintype "passive"))
    )
    (net (code "44") (name "/MIPI_DAT2_N") (class "Default")
      (node (ref "U1") (pin "J9") (pinfunction "MIPI_D2N_J9") (pintype "passive"))
    )
    (net (code "45") (name "/MIPI_DAT2_P") (class "Default")
      (node (ref "U1") (pin "J8") (pinfunction "MIPI_D2P_J8") (pintype "passive"))
    )
    (net (code "46") (name "/MIPI_DAT3_N") (class "Default")
      (node (ref "U1") (pin "K8") (pinfunction "MIPI_D3N_K8") (pintype "passive"))
    )
    (net (code "47") (name "/MIPI_DAT3_P") (class "Default")
      (node (ref "U1") (pin "L8") (pinfunction "MIPI_D3P_L8") (pintype "passive"))
    )
    (net (code "48") (name "/USB2_DATA_N") (class "Default")
      (node (ref "TS3") (pin "2") (pintype "passive"))
      (node (ref "U1") (pin "A10") (pinfunction "DM_A10") (pintype "passive"))
    )
    (net (code "49") (name "/USB2_DATA_P") (class "Default")
      (node (ref "TS3") (pin "4") (pintype "passive"))
      (node (ref "U1") (pin "A9") (pinfunction "DP_A9") (pintype "passive"))
    )
    (net (code "50") (name "/USB_SSRX_N") (class "Default")
      (node (ref "TS1") (pin "6") (pinfunction "NC3_6") (pintype "passive"))
      (node (ref "U1") (pin "A3") (pinfunction "SSRXM_A3") (pintype "passive"))
    )
    (net (code "51") (name "/USB_SSRX_P") (class "Default")
      (node (ref "TS1") (pin "5") (pinfunction "NC4_5") (pintype "passive"))
      (node (ref "U1") (pin "A4") (pinfunction "SSRXP_A4") (pintype "passive"))
    )
    (net (code "52") (name "/USB_SSTX_N") (class "Default")
      (node (ref "C8") (pin "2") (pinfunction "2_2") (pintype "passive"))
      (node (ref "TS1") (pin "8") (pinfunction "NC1_8") (pintype "passive"))
    )
    (net (code "53") (name "/USB_SSTX_P") (class "Default")
      (node (ref "C9") (pin "2") (pinfunction "2_2") (pintype "passive"))
      (node (ref "TS1") (pin "7") (pinfunction "NC2_7") (pintype "passive"))
    )
    (net (code "54") (name "/VCC1P2_A") (class "Default")
      (node (ref "C13") (pin "2") (pinfunction "2_2") (pintype "passive"))
      (node (ref "C14") (pin "1") (pinfunction "1_1") (pintype "passive"))
      (node (ref "L2") (pin "2") (pinfunction "2_2") (pintype "passive"))
      (node (ref "U1") (pin "A7") (pinfunction "AVDD_A7") (pintype "passive"))
    )
    (net (code "55") (name "/VCC1P2_FX3_RX") (class "Default")
      (node (ref "C29") (pin "2") (pinfunction "2_2") (pintype "passive"))
      (node (ref "C30") (pin "1") (pinfunction "1_1") (pintype "passive"))
      (node (ref "L4") (pin "2") (pinfunction "2_2") (pintype "passive"))
      (node (ref "U1") (pin "A2") (pinfunction "U3RXVDDQ_A2") (pintype "passive"))
    )
    (net (code "56") (name "/VCC1P2_FX3_TX") (class "Default")
      (node (ref "C27") (pin "2") (pinfunction "2_2") (pintype "passive"))
      (node (ref "C28") (pin "1") (pinfunction "1_1") (pintype "passive"))
      (node (ref "L3") (pin "2") (pinfunction "2_2") (pintype "passive"))
      (node (ref "U1") (pin "B5") (pinfunction "U3TXVDDQ_B5") (pintype "passive"))
    )
    (net (code "57") (name "/nRST_CAM") (class "Default")
      (node (ref "R5") (pin "2") (pinfunction "2_2") (pintype "passive"))
      (node (ref "U1") (pin "H6") (pinfunction "MIPI_RESET_H6") (pintype "passive"))
    )
    (net (code "58") (name "GND") (class "Default")
      (node (ref "C1") (pin "2") (pinfunction "2_2") (pintype "passive"))
      (node (ref "C10") (pin "2") (pinfunction "2_2") (pintype "passive"))
      (node (ref "C11") (pin "1") (pinfunction "1_1") (pintype "passive"))
      (node (ref "C12") (pin "2") (pinfunction "2_2") (pintype "passive"))
      (node (ref "C13") (pin "1") (pinfunction "1_1") (pintype "passive"))
      (node (ref "C14") (pin "2") (pinfunction "2_2") (pintype "passive"))
      (node (ref "C15") (pin "1") (pinfunction "1_1") (pintype "passive"))
      (node (ref "C16") (pin "1") (pinfunction "1_1") (pintype "passive"))
      (node (ref "C17") (pin "1") (pinfunction "1_1") (pintype "passive"))
      (node (ref "C18") (pin "1") (pinfunction "1_1") (pintype "passive"))
      (node (ref "C19") (pin "1") (pinfunction "1_1") (pintype "passive"))
      (node (ref "C2") (pin "2") (pinfunction "2_2") (pintype "passive"))
      (node (ref "C20") (pin "1") (pinfunction "1_1") (pintype "passive"))
      (node (ref "C21") (pin "1") (pinfunction "1_1") (pintype "passive"))
      (node (ref "C22") (pin "1") (pinfunction "1_1") (pintype "passive"))
      (node (ref "C23") (pin "1") (pinfunction "1_1") (pintype "passive"))
      (node (ref "C24") (pin "1") (pinfunction "1_1") (pintype "passive"))
      (node (ref "C25") (pin "1") (pinfunction "1_1") (pintype "passive"))
      (node (ref "C26") (pin "1") (pinfunction "1_1") (pintype "passive"))
      (node (ref "C27") (pin "1") (pinfunction "1_1") (pintype "passive"))
      (node (ref "C28") (pin "2") (pinfunction "2_2") (pintype "passive"))
      (node (ref "C29") (pin "1") (pinfunction "1_1") (pintype "passive"))
      (node (ref "C3") (pin "2") (pinfunction "2_2") (pintype "passive"))
      (node (ref "C30") (pin "2") (pinfunction "2_2") (pintype "passive"))
      (node (ref "C31") (pin "2") (pinfunction "2_2") (pintype "passive"))
      (node (ref "C32") (pin "1") (pinfunction "1_1") (pintype "passive"))
      (node (ref "C33") (pin "1") (pinfunction "1_1") (pintype "passive"))
      (node (ref "C34") (pin "2") (pinfunction "2_2") (pintype "passive"))
      (node (ref "C35") (pin "1") (pinfunction "1_1") (pintype "passive"))
      (node (ref "C36") (pin "1") (pinfunction "1_1") (pintype "passive"))
      (node (ref "C37") (pin "1") (pinfunction "1_1") (pintype "passive"))
      (node (ref "C38") (pin "1") (pinfunction "1_1") (pintype "passive"))
      (node (ref "C39") (pin "2") (pinfunction "2_2") (pintype "passive"))
      (node (ref "C4") (pin "2") (pinfunction "2_2") (pintype "passive"))
      (node (ref "C42") (pin "1") (pinfunction "1_1") (pintype "passive"))
      (node (ref "C43") (pin "1") (pinfunction "1_1") (pintype "passive"))
      (node (ref "C44") (pin "1") (pinfunction "1_1") (pintype "passive"))
      (node (ref "C45") (pin "1") (pinfunction "1_1") (pintype "passive"))
      (node (ref "C46") (pin "1") (pinfunction "1_1") (pintype "passive"))
      (node (ref "C47") (pin "1") (pinfunction "1_1") (pintype "passive"))
      (node (ref "C48") (pin "1") (pinfunction "1_1") (pintype "passive"))
      (node (ref "C49") (pin "1") (pinfunction "1_1") (pintype "passive"))
      (node (ref "C5") (pin "2") (pinfunction "2_2") (pintype "passive"))
      (node (ref "C50") (pin "1") (pinfunction "1_1") (pintype "passive"))
      (node (ref "C51") (pin "1") (pinfunction "1_1") (pintype "passive"))
      (node (ref "C52") (pin "1") (pinfunction "1_1") (pintype "passive"))
      (node (ref "C53") (pin "2") (pinfunction "2_2") (pintype "passive"))
      (node (ref "C54") (pin "1") (pinfunction "1_1") (pintype "passive"))
      (node (ref "C55") (pin "2") (pinfunction "2_2") (pintype "passive"))
      (node (ref "C57") (pin "1") (pinfunction "1_1") (pintype "passive"))
      (node (ref "C58") (pin "2") (pinfunction "2_2") (pintype "passive"))
      (node (ref "C6") (pin "2") (pinfunction "2_2") (pintype "passive"))
      (node (ref "C7") (pin "1") (pinfunction "1_1") (pintype "passive"))
      (node (ref "CN1") (pin "5") (pinfunction "GND_5") (pintype "passive"))
      (node (ref "CN1") (pin "8") (pinfunction "GND_8") (pintype "passive"))
      (node (ref "CN3") (pin "3") (pinfunction "3_3") (pintype "passive"))
      (node (ref "CN3") (pin "5") (pinfunction "5_5") (pintype "passive"))
      (node (ref "CN3") (pin "9") (pinfunction "9_9") (pintype "passive"))
      (node (ref "D2") (pin "2") (pinfunction "A_2") (pintype "passive"))
      (node (ref "FB2") (pin "2") (pinfunction "2_2") (pintype "passive"))
      (node (ref "FB5") (pin "2") (pinfunction "2_2") (pintype "passive"))
      (node (ref "FB7") (pin "2") (pinfunction "2_2") (pintype "passive"))
      (node (ref "R17") (pin "2") (pinfunction "2_2") (pintype "passive"))
      (node (ref "R20") (pin "1") (pinfunction "1_1") (pintype "passive"))
      (node (ref "R23") (pin "2") (pinfunction "2_2") (pintype "passive"))
      (node (ref "R26") (pin "2") (pinfunction "2_2") (pintype "passive"))
      (node (ref "R29") (pin "1") (pinfunction "1_1") (pintype "passive"))
      (node (ref "R5") (pin "1") (pinfunction "1_1") (pintype "passive"))
      (node (ref "R7") (pin "2") (pinfunction "2_2") (pintype "passive"))
      (node (ref "TS1") (pin "9") (pinfunction "GND_9") (pintype "passive"))
      (node (ref "TS2") (pin "1") (pinfunction "A_1") (pintype "passive"))
      (node (ref "TS4") (pin "3") (pintype "passive"))
      (node (ref "U1") (pin "A1") (pinfunction "U3VSSQ_A1") (pintype "passive"))
      (node (ref "U1") (pin "A8") (pinfunction "VSS_A8") (pintype "passive"))
      (node (ref "U1") (pin "B2") (pinfunction "VSS_B2") (pintype "passive"))
      (node (ref "U1") (pin "B7") (pinfunction "AVSS_B7") (pintype "passive"))
      (node (ref "U1") (pin "B8") (pinfunction "VSS_B8") (pintype "passive"))
      (node (ref "U1") (pin "B9") (pinfunction "VSS_B9") (pintype "passive"))
      (node (ref "U1") (pin "D8") (pinfunction "VSS_D8") (pintype "passive"))
      (node (ref "U1") (pin "E11") (pinfunction "VSS_E11") (pintype "passive"))
      (node (ref "U1") (pin "E2") (pinfunction "VSS_E2") (pintype "passive"))
      (node (ref "U1") (pin "G1") (pinfunction "VSS_G1") (pintype "passive"))
      (node (ref "U1") (pin "G11") (pinfunction "VSS_G11") (pintype "passive"))
      (node (ref "U1") (pin "K3") (pinfunction "VSS_K3") (pintype "passive"))
      (node (ref "U1") (pin "K4") (pinfunction "VSS_K4") (pintype "passive"))
      (node (ref "U1") (pin "L1") (pinfunction "VSS_L1") (pintype "passive"))
      (node (ref "U1") (pin "L11") (pinfunction "VSS_L11") (pintype "passive"))
      (node (ref "U1") (pin "L2") (pinfunction "VSS_L2") (pintype "passive"))
      (node (ref "U1") (pin "L3") (pinfunction "VSS_L3") (pintype "passive"))
      (node (ref "U1") (pin "L6") (pinfunction "VSS_L6") (pintype "passive"))
      (node (ref "U10") (pin "3") (pinfunction "GND_3") (pintype "passive"))
      (node (ref "U10") (pin "4") (pinfunction "GND_4") (pintype "passive"))
      (node (ref "U10") (pin "5") (pinfunction "GND_5") (pintype "passive"))
      (node (ref "U10") (pin "6") (pinfunction "VDD_6") (pintype "passive"))
      (node (ref "U2") (pin "2") (pinfunction "GND_2") (pintype "passive"))
      (node (ref "U2") (pin "3") (pinfunction "EN_3") (pintype "passive"))
      (node (ref "U3") (pin "2") (pinfunction "GND_2") (pintype "passive"))
      (node (ref "U4") (pin "3") (pinfunction "W_3") (pintype "passive"))
      (node (ref "U4") (pin "4") (pinfunction "VSS_4") (pintype "passive"))
      (node (ref "U5") (pin "12") (pinfunction "GND_12") (pintype "power_in"))
      (node (ref "U5") (pin "21") (pinfunction "EPAD_21") (pintype "passive"))
      (node (ref "U6") (pin "2") (pinfunction "GND_2") (pintype "power_in"))
      (node (ref "U6") (pin "7") (pinfunction "EPAD_7") (pintype "passive"))
      (node (ref "U7") (pin "12") (pinfunction "GND_12") (pintype "power_in"))
      (node (ref "U7") (pin "21") (pinfunction "EPAD_21") (pintype "passive"))
      (node (ref "U8") (pin "12") (pinfunction "GND_12") (pintype "power_in"))
      (node (ref "U8") (pin "21") (pinfunction "EPAD_21") (pintype "passive"))
      (node (ref "U9") (pin "3") (pinfunction "GND_3") (pintype "passive"))
      (node (ref "U9") (pin "4") (pinfunction "GND_4") (pintype "passive"))
      (node (ref "U9") (pin "5") (pinfunction "GND_5") (pintype "passive"))
      (node (ref "U9") (pin "6") (pinfunction "VDD_6") (pintype "passive"))
      (node (ref "Y1") (pin "2") (pinfunction "GND_2") (pintype "passive"))
      (node (ref "Y2") (pin "2") (pinfunction "GND_2") (pintype "passive"))
    )
    (net (code "59") (name "Net-(CN1-D+)") (class "Default")
      (node (ref "CN1") (pin "3") (pinfunction "D+_3") (pintype "passive"))
      (node (ref "TS3") (pin "3") (pintype "passive"))
    )
    (net (code "60") (name "Net-(CN1-D-)") (class "Default")
      (node (ref "CN1") (pin "2") (pinfunction "D-_2") (pintype "passive"))
      (node (ref "TS3") (pin "1") (pintype "passive"))
    )
    (net (code "61") (name "Net-(CN1-SHIELD)") (class "Default")
      (node (ref "C31") (pin "1") (pinfunction "1_1") (pintype "passive"))
      (node (ref "CN1") (pin "0") (pinfunction "SHIELD_0") (pintype "passive"))
      (node (ref "R7") (pin "1") (pinfunction "1_1") (pintype "passive"))
    )
    (net (code "62") (name "Net-(CN1-SSRX+)") (class "Default")
      (node (ref "CN1") (pin "10") (pinfunction "SSRX+_10") (pintype "passive"))
      (node (ref "TS1") (pin "4") (pinfunction "IN4_4") (pintype "passive"))
    )
    (net (code "63") (name "Net-(CN1-SSRX-)") (class "Default")
      (node (ref "CN1") (pin "9") (pinfunction "SSRX-_9") (pintype "passive"))
      (node (ref "TS1") (pin "3") (pinfunction "IN3_3") (pintype "passive"))
    )
    (net (code "64") (name "Net-(CN1-SSTX+)") (class "Default")
      (node (ref "CN1") (pin "7") (pinfunction "SSTX+_7") (pintype "passive"))
      (node (ref "TS1") (pin "2") (pinfunction "IN2_2") (pintype "passive"))
    )
    (net (code "65") (name "Net-(CN1-SSTX-)") (class "Default")
      (node (ref "CN1") (pin "6") (pinfunction "SSTX-_6") (pintype "passive"))
      (node (ref "TS1") (pin "1") (pinfunction "IN1_1") (pintype "passive"))
    )
    (net (code "66") (name "Net-(CN1-VBUS)") (class "Default")
      (node (ref "CN1") (pin "1") (pinfunction "VBUS_1") (pintype "passive"))
      (node (ref "FB1") (pin "1") (pinfunction "1_1") (pintype "passive"))
      (node (ref "TS2") (pin "2") (pinfunction "K_2") (pintype "passive"))
    )
    (net (code "67") (name "Net-(CN4-Pad2)") (class "Default")
      (node (ref "CN4") (pin "2") (pinfunction "2_2") (pintype "passive"))
      (node (ref "FB7") (pin "1") (pinfunction "1_1") (pintype "passive"))
    )
    (net (code "68") (name "Net-(CN4-Pad5)") (class "Default")
      (node (ref "CN4") (pin "5") (pinfunction "5_5") (pintype "passive"))
      (node (ref "FB6") (pin "1") (pinfunction "1_1") (pintype "passive"))
    )
    (net (code "69") (name "Net-(CN4-Pad8)") (class "Default")
      (node (ref "CN4") (pin "8") (pinfunction "8_8") (pintype "passive"))
      (node (ref "FB5") (pin "1") (pinfunction "1_1") (pintype "passive"))
    )
    (net (code "70") (name "Net-(CN5-Pad4)") (class "Default")
      (node (ref "CN5") (pin "4") (pinfunction "4_4") (pintype "passive"))
      (node (ref "FB4") (pin "1") (pinfunction "1_1") (pintype "passive"))
    )
    (net (code "71") (name "Net-(CN5-Pad6)") (class "Default")
      (node (ref "CN5") (pin "6") (pinfunction "6_6") (pintype "passive"))
      (node (ref "FB3") (pin "1") (pinfunction "1_1") (pintype "passive"))
    )
    (net (code "72") (name "Net-(CN5-Pad8)") (class "Default")
      (node (ref "CN5") (pin "8") (pinfunction "8_8") (pintype "passive"))
      (node (ref "FB2") (pin "1") (pinfunction "1_1") (pintype "passive"))
    )
    (net (code "73") (name "Net-(D1-K)") (class "Default")
      (node (ref "C40") (pin "1") (pinfunction "1_1") (pintype "passive"))
      (node (ref "D1") (pin "1") (pinfunction "K_1") (pintype "passive"))
      (node (ref "U6") (pin "3") (pinfunction "BOOST_3") (pintype "input"))
    )
    (net (code "74") (name "Net-(D3-A)") (class "Default")
      (node (ref "CN2") (pin "2") (pinfunction "2_2") (pintype "power_in"))
      (node (ref "CN2") (pin "2A") (pinfunction "2A_2A") (pintype "power_in"))
      (node (ref "CN2") (pin "2B") (pinfunction "2B_2B") (pintype "power_in"))
      (node (ref "CN2") (pin "3") (pinfunction "3_3") (pintype "power_in"))
      (node (ref "CN2") (pin "3A") (pinfunction "3A_3A") (pintype "power_in"))
      (node (ref "CN2") (pin "3B") (pinfunction "3B_3B") (pintype "power_in"))
      (node (ref "D3") (pin "2") (pinfunction "A_2") (pintype "passive"))
      (node (ref "TS4") (pin "4") (pintype "passive"))
    )
    (net (code "75") (name "Net-(D3-K)") (class "Default")
      (node (ref "CN2") (pin "1") (pinfunction "1_1") (pintype "power_in"))
      (node (ref "CN2") (pin "1A") (pinfunction "1A_1A") (pintype "power_in"))
      (node (ref "CN2") (pin "1B") (pinfunction "1B_1B") (pintype "power_in"))
      (node (ref "D3") (pin "1") (pinfunction "K_1") (pintype "passive"))
      (node (ref "TS4") (pin "2") (pintype "passive"))
    )
    (net (code "76") (name "Net-(R27-Pad2)") (class "Default")
      (node (ref "R27") (pin "2") (pinfunction "2_2") (pintype "passive"))
      (node (ref "SW2") (pin "3") (pinfunction "3_3") (pintype "passive"))
    )
    (net (code "77") (name "Net-(R28-Pad2)") (class "Default")
      (node (ref "R28") (pin "2") (pinfunction "2_2") (pintype "passive"))
      (node (ref "SW2") (pin "1") (pinfunction "1_1") (pintype "passive"))
    )
    (net (code "78") (name "Net-(R29-Pad2)") (class "Default")
      (node (ref "R29") (pin "2") (pinfunction "2_2") (pintype "passive"))
      (node (ref "SW2") (pin "5") (pinfunction "5_5") (pintype "passive"))
    )
    (net (code "79") (name "Net-(U1A-INT#)") (class "Default")
      (node (ref "R6") (pin "2") (pinfunction "2_2") (pintype "passive"))
      (node (ref "U1") (pin "F1") (pinfunction "INT#_F1") (pintype "passive"))
    )
    (net (code "80") (name "Net-(U1A-SPI_SCK)") (class "Default")
      (node (ref "R1") (pin "2") (pinfunction "2_2") (pintype "passive"))
      (node (ref "U1") (pin "D4") (pinfunction "SPI_SCK_D4") (pintype "passive"))
    )
    (net (code "81") (name "Net-(U1B-SSTXM)") (class "Default")
      (node (ref "C8") (pin "1") (pinfunction "1_1") (pintype "passive"))
      (node (ref "U1") (pin "A6") (pinfunction "SSTXM_A6") (pintype "passive"))
    )
    (net (code "82") (name "Net-(U1B-SSTXP)") (class "Default")
      (node (ref "C9") (pin "1") (pinfunction "1_1") (pintype "passive"))
      (node (ref "U1") (pin "A5") (pinfunction "SSTXP_A5") (pintype "passive"))
    )
    (net (code "83") (name "Net-(U2-FLAG)") (class "Default")
      (node (ref "R8") (pin "1") (pinfunction "1_1") (pintype "passive"))
      (node (ref "U2") (pin "4") (pinfunction "FLAG_4") (pintype "passive"))
    )
    (net (code "84") (name "Net-(U3-1A)") (class "Default")
      (node (ref "R9") (pin "2") (pinfunction "2_2") (pintype "passive"))
      (node (ref "U3") (pin "1") (pinfunction "1A_1") (pintype "passive"))
      (node (ref "U3") (pin "3") (pinfunction "2A_3") (pintype "passive"))
    )
    (net (code "85") (name "Net-(U3-1Y)") (class "Default")
      (node (ref "R11") (pin "2") (pinfunction "2_2") (pintype "passive"))
      (node (ref "U3") (pin "6") (pinfunction "1Y_6") (pintype "passive"))
    )
    (net (code "86") (name "Net-(U3-2Y)") (class "Default")
      (node (ref "R10") (pin "2") (pinfunction "2_2") (pintype "passive"))
      (node (ref "U3") (pin "4") (pinfunction "2Y_4") (pintype "passive"))
    )
    (net (code "87") (name "Net-(U4-HOLD)") (class "Default")
      (node (ref "R12") (pin "1") (pinfunction "1_1") (pintype "passive"))
      (node (ref "U4") (pin "7") (pinfunction "HOLD_7") (pintype "passive"))
    )
    (net (code "88") (name "Net-(U5-FB)") (class "Default")
      (node (ref "R16") (pin "2") (pinfunction "2_2") (pintype "passive"))
      (node (ref "R17") (pin "1") (pinfunction "1_1") (pintype "passive"))
      (node (ref "U5") (pin "16") (pinfunction "FB_16") (pintype "passive"))
    )
    (net (code "89") (name "Net-(U5-PG)") (class "Default")
      (node (ref "R15") (pin "2") (pinfunction "2_2") (pintype "passive"))
      (node (ref "U5") (pin "9") (pinfunction "PG_9") (pintype "passive"))
    )
    (net (code "90") (name "Net-(U5-SS)") (class "Default")
      (node (ref "C36") (pin "2") (pinfunction "2_2") (pintype "passive"))
      (node (ref "U5") (pin "15") (pinfunction "SS_15") (pintype "passive"))
    )
    (net (code "91") (name "Net-(U6-*SHDN)") (class "Default")
      (node (ref "R18") (pin "2") (pinfunction "2_2") (pintype "passive"))
      (node (ref "U6") (pin "6") (pinfunction "*SHDN_6") (pintype "passive"))
    )
    (net (code "92") (name "Net-(U6-FB)") (class "Default")
      (node (ref "C41") (pin "2") (pinfunction "2_2") (pintype "passive"))
      (node (ref "R19") (pin "2") (pinfunction "2_2") (pintype "passive"))
      (node (ref "R20") (pin "2") (pinfunction "2_2") (pintype "passive"))
      (node (ref "U6") (pin "1") (pinfunction "FB_1") (pintype "output"))
    )
    (net (code "93") (name "Net-(U7-FB)") (class "Default")
      (node (ref "R22") (pin "2") (pinfunction "2_2") (pintype "passive"))
      (node (ref "R23") (pin "1") (pinfunction "1_1") (pintype "passive"))
      (node (ref "U7") (pin "16") (pinfunction "FB_16") (pintype "passive"))
    )
    (net (code "94") (name "Net-(U7-PG)") (class "Default")
      (node (ref "R21") (pin "2") (pinfunction "2_2") (pintype "passive"))
      (node (ref "U7") (pin "9") (pinfunction "PG_9") (pintype "passive"))
    )
    (net (code "95") (name "Net-(U7-SS)") (class "Default")
      (node (ref "C44") (pin "2") (pinfunction "2_2") (pintype "passive"))
      (node (ref "U7") (pin "15") (pinfunction "SS_15") (pintype "passive"))
    )
    (net (code "96") (name "Net-(U8-FB)") (class "Default")
      (node (ref "R25") (pin "2") (pinfunction "2_2") (pintype "passive"))
      (node (ref "R26") (pin "1") (pinfunction "1_1") (pintype "passive"))
      (node (ref "U8") (pin "16") (pinfunction "FB_16") (pintype "passive"))
    )
    (net (code "97") (name "Net-(U8-PG)") (class "Default")
      (node (ref "R24") (pin "2") (pinfunction "2_2") (pintype "passive"))
      (node (ref "U8") (pin "9") (pinfunction "PG_9") (pintype "passive"))
    )
    (net (code "98") (name "Net-(Y2-CLK_OUT)") (class "Default")
      (node (ref "R9") (pin "1") (pinfunction "1_1") (pintype "passive"))
      (node (ref "Y2") (pin "3") (pinfunction "CLK_OUT_3") (pintype "passive"))
    )
    (net (code "99") (name "Net-(Y2-EN)") (class "Default")
      (node (ref "R30") (pin "1") (pinfunction "1_1") (pintype "passive"))
      (node (ref "Y2") (pin "1") (pinfunction "EN_1") (pintype "passive"))
    )
    (net (code "100") (name "VCCIO_CLK") (class "Default")
      (node (ref "C11") (pin "2") (pinfunction "2_2") (pintype "passive"))
      (node (ref "C12") (pin "1") (pinfunction "1_1") (pintype "passive"))
      (node (ref "C57") (pin "2") (pinfunction "2_2") (pintype "passive"))
      (node (ref "C58") (pin "1") (pinfunction "1_1") (pintype "passive"))
      (node (ref "L1") (pin "2") (pinfunction "2_2") (pintype "passive"))
      (node (ref "R30") (pin "2") (pinfunction "2_2") (pintype "passive"))
      (node (ref "U1") (pin "B6") (pinfunction "CVDDQ_B6") (pintype "passive"))
      (node (ref "U3") (pin "5") (pinfunction "VCC_5") (pintype "passive"))
      (node (ref "Y1") (pin "4") (pinfunction "VDD_4") (pintype "passive"))
      (node (ref "Y2") (pin "4") (pinfunction "VDD_4") (pintype "passive"))
    )
    (net (code "101") (name "VCC_1V2") (class "Default")
      (node (ref "C10") (pin "1") (pinfunction "1_1") (pintype "passive"))
      (node (ref "C15") (pin "2") (pinfunction "2_2") (pintype "passive"))
      (node (ref "C16") (pin "2") (pinfunction "2_2") (pintype "passive"))
      (node (ref "C17") (pin "2") (pinfunction "2_2") (pintype "passive"))
      (node (ref "C18") (pin "2") (pinfunction "2_2") (pintype "passive"))
      (node (ref "C19") (pin "2") (pinfunction "2_2") (pintype "passive"))
      (node (ref "C20") (pin "2") (pinfunction "2_2") (pintype "passive"))
      (node (ref "C21") (pin "2") (pinfunction "2_2") (pintype "passive"))
      (node (ref "C22") (pin "2") (pinfunction "2_2") (pintype "passive"))
      (node (ref "C23") (pin "2") (pinfunction "2_2") (pintype "passive"))
      (node (ref "C24") (pin "2") (pinfunction "2_2") (pintype "passive"))
      (node (ref "C25") (pin "2") (pinfunction "2_2") (pintype "passive"))
      (node (ref "C26") (pin "2") (pinfunction "2_2") (pintype "passive"))
      (node (ref "C48") (pin "2") (pinfunction "2_2") (pintype "passive"))
      (node (ref "C49") (pin "2") (pinfunction "2_2") (pintype "passive"))
      (node (ref "L2") (pin "1") (pinfunction "1_1") (pintype "passive"))
      (node (ref "L3") (pin "1") (pinfunction "1_1") (pintype "passive"))
      (node (ref "L4") (pin "1") (pinfunction "1_1") (pintype "passive"))
      (node (ref "R24") (pin "1") (pinfunction "1_1") (pintype "passive"))
      (node (ref "R25") (pin "1") (pinfunction "1_1") (pintype "passive"))
      (node (ref "U1") (pin "B10") (pinfunction "VDD_B10") (pintype "passive"))
      (node (ref "U1") (pin "C3") (pinfunction "VDD_C3") (pintype "passive"))
      (node (ref "U1") (pin "E9") (pinfunction "VDD_E9") (pintype "passive"))
      (node (ref "U1") (pin "F11") (pinfunction "VDD_F11") (pintype "passive"))
      (node (ref "U1") (pin "H1") (pinfunction "VDD_H1") (pintype "passive"))
      (node (ref "U1") (pin "J11") (pinfunction "VDD_J11") (pintype "passive"))
      (node (ref "U1") (pin "L5") (pinfunction "MIPI_VDD_L5") (pintype "passive"))
      (node (ref "U1") (pin "L7") (pinfunction "VDD_L7") (pintype "passive"))
      (node (ref "U8") (pin "1") (pinfunction "OUT_1") (pintype "output"))
      (node (ref "U8") (pin "18") (pinfunction "OUT_18") (pintype "output"))
      (node (ref "U8") (pin "19") (pinfunction "OUT_19") (pintype "output"))
      (node (ref "U8") (pin "20") (pinfunction "OUT_20") (pintype "output"))
    )
    (net (code "102") (name "VCC_1V8") (class "Default")
      (node (ref "C41") (pin "1") (pinfunction "1_1") (pintype "passive"))
      (node (ref "C42") (pin "2") (pinfunction "2_2") (pintype "passive"))
      (node (ref "C54") (pin "2") (pinfunction "2_2") (pintype "passive"))
      (node (ref "FB4") (pin "2") (pinfunction "2_2") (pintype "passive"))
      (node (ref "L5") (pin "2") (pinfunction "2_2") (pintype "passive"))
      (node (ref "R19") (pin "1") (pinfunction "1_1") (pintype "passive"))
    )
    (net (code "103") (name "VCC_1V8FB") (class "Default")
      (node (ref "C40") (pin "2") (pinfunction "2_2") (pintype "passive"))
      (node (ref "D2") (pin "1") (pinfunction "K_1") (pintype "passive"))
      (node (ref "L5") (pin "1") (pinfunction "1_1") (pintype "passive"))
      (node (ref "U6") (pin "4") (pinfunction "SW_4") (pintype "output"))
    )
    (net (code "104") (name "VCC_2V8") (class "Default")
      (node (ref "C45") (pin "2") (pinfunction "2_2") (pintype "passive"))
      (node (ref "C46") (pin "2") (pinfunction "2_2") (pintype "passive"))
      (node (ref "C55") (pin "1") (pinfunction "1_1") (pintype "passive"))
      (node (ref "FB6") (pin "2") (pinfunction "2_2") (pintype "passive"))
      (node (ref "R21") (pin "1") (pinfunction "1_1") (pintype "passive"))
      (node (ref "R22") (pin "1") (pinfunction "1_1") (pintype "passive"))
      (node (ref "U7") (pin "1") (pinfunction "OUT_1") (pintype "output"))
      (node (ref "U7") (pin "18") (pinfunction "OUT_18") (pintype "output"))
      (node (ref "U7") (pin "19") (pinfunction "OUT_19") (pintype "output"))
      (node (ref "U7") (pin "20") (pinfunction "OUT_20") (pintype "output"))
    )
    (net (code "105") (name "VCC_5V") (class "Default")
      (node (ref "C50") (pin "2") (pinfunction "2_2") (pintype "passive"))
      (node (ref "SW1") (pin "1") (pinfunction "1_1") (pintype "passive"))
      (node (ref "TS4") (pin "1") (pintype "passive"))
    )
    (net (code "106") (name "VCC_IO") (class "Default")
      (node (ref "C1") (pin "1") (pinfunction "1_1") (pintype "passive"))
      (node (ref "C2") (pin "1") (pinfunction "1_1") (pintype "passive"))
      (node (ref "C3") (pin "1") (pinfunction "1_1") (pintype "passive"))
      (node (ref "C34") (pin "1") (pinfunction "1_1") (pintype "passive"))
      (node (ref "C37") (pin "2") (pinfunction "2_2") (pintype "passive"))
      (node (ref "C38") (pin "2") (pinfunction "2_2") (pintype "passive"))
      (node (ref "C4") (pin "1") (pinfunction "1_1") (pintype "passive"))
      (node (ref "C5") (pin "1") (pinfunction "1_1") (pintype "passive"))
      (node (ref "C53") (pin "1") (pinfunction "1_1") (pintype "passive"))
      (node (ref "C6") (pin "1") (pinfunction "1_1") (pintype "passive"))
      (node (ref "CN3") (pin "1") (pinfunction "1_1") (pintype "passive"))
      (node (ref "CN4") (pin "1") (pinfunction "1_1") (pintype "passive"))
      (node (ref "FB3") (pin "2") (pinfunction "2_2") (pintype "passive"))
      (node (ref "L1") (pin "1") (pinfunction "1_1") (pintype "passive"))
      (node (ref "R12") (pin "2") (pinfunction "2_2") (pintype "passive"))
      (node (ref "R13") (pin "2") (pinfunction "2_2") (pintype "passive"))
      (node (ref "R14") (pin "2") (pinfunction "2_2") (pintype "passive"))
      (node (ref "R15") (pin "1") (pinfunction "1_1") (pintype "passive"))
      (node (ref "R16") (pin "1") (pinfunction "1_1") (pintype "passive"))
      (node (ref "R27") (pin "1") (pinfunction "1_1") (pintype "passive"))
      (node (ref "R28") (pin "1") (pinfunction "1_1") (pintype "passive"))
      (node (ref "R6") (pin "1") (pinfunction "1_1") (pintype "passive"))
      (node (ref "U1") (pin "B1") (pinfunction "VDDIO3_B1") (pintype "passive"))
      (node (ref "U1") (pin "E3") (pinfunction "VDDIO2_E3") (pintype "passive"))
      (node (ref "U1") (pin "H11") (pinfunction "VDDIO1_H11") (pintype "passive"))
      (node (ref "U1") (pin "L9") (pinfunction "VDDIO1_L9") (pintype "passive"))
      (node (ref "U4") (pin "8") (pinfunction "VCC_8") (pintype "passive"))
      (node (ref "U5") (pin "1") (pinfunction "OUT_1") (pintype "output"))
      (node (ref "U5") (pin "18") (pinfunction "OUT_18") (pintype "output"))
      (node (ref "U5") (pin "19") (pinfunction "OUT_19") (pintype "output"))
      (node (ref "U5") (pin "20") (pinfunction "OUT_20") (pintype "output"))
    )
    (net (code "107") (name "VCC_SYS") (class "Default")
      (node (ref "C35") (pin "2") (pinfunction "2_2") (pintype "passive"))
      (node (ref "C39") (pin "1") (pinfunction "1_1") (pintype "passive"))
      (node (ref "C43") (pin "2") (pinfunction "2_2") (pintype "passive"))
      (node (ref "C47") (pin "2") (pinfunction "2_2") (pintype "passive"))
      (node (ref "C52") (pin "2") (pinfunction "2_2") (pintype "passive"))
      (node (ref "D1") (pin "2") (pinfunction "A_2") (pintype "passive"))
      (node (ref "R18") (pin "1") (pinfunction "1_1") (pintype "passive"))
      (node (ref "SW1") (pin "2") (pinfunction "2_2") (pintype "passive"))
      (node (ref "U5") (pin "10") (pinfunction "BIAS_10") (pintype "passive"))
      (node (ref "U5") (pin "11") (pinfunction "EN_11") (pintype "passive"))
      (node (ref "U5") (pin "5") (pinfunction "IN_5") (pintype "input"))
      (node (ref "U5") (pin "6") (pinfunction "IN_6") (pintype "input"))
      (node (ref "U5") (pin "7") (pinfunction "IN_7") (pintype "input"))
      (node (ref "U5") (pin "8") (pinfunction "IN_8") (pintype "input"))
      (node (ref "U6") (pin "5") (pinfunction "VIN_5") (pintype "input"))
      (node (ref "U7") (pin "10") (pinfunction "BIAS_10") (pintype "passive"))
      (node (ref "U7") (pin "11") (pinfunction "EN_11") (pintype "passive"))
      (node (ref "U7") (pin "5") (pinfunction "IN_5") (pintype "input"))
      (node (ref "U7") (pin "6") (pinfunction "IN_6") (pintype "input"))
      (node (ref "U7") (pin "7") (pinfunction "IN_7") (pintype "input"))
      (node (ref "U7") (pin "8") (pinfunction "IN_8") (pintype "input"))
      (node (ref "U8") (pin "10") (pinfunction "BIAS_10") (pintype "passive"))
      (node (ref "U8") (pin "11") (pinfunction "EN_11") (pintype "passive"))
      (node (ref "U8") (pin "5") (pinfunction "IN_5") (pintype "input"))
      (node (ref "U8") (pin "6") (pinfunction "IN_6") (pintype "input"))
      (node (ref "U8") (pin "7") (pinfunction "IN_7") (pintype "input"))
      (node (ref "U8") (pin "8") (pinfunction "IN_8") (pintype "input"))
    )
    (net (code "108") (name "VCC_USB") (class "Default")
      (node (ref "C51") (pin "2") (pinfunction "2_2") (pintype "passive"))
      (node (ref "C7") (pin "2") (pinfunction "2_2") (pintype "passive"))
      (node (ref "SW1") (pin "3") (pinfunction "3_3") (pintype "passive"))
      (node (ref "U1") (pin "E10") (pinfunction "VUSB_E10") (pintype "passive"))
      (node (ref "U2") (pin "5") (pinfunction "OUT_5") (pintype "passive"))
    )
    (net (code "109") (name "VCC_USB_RAW") (class "Default")
      (node (ref "C32") (pin "2") (pinfunction "2_2") (pintype "passive"))
      (node (ref "C33") (pin "2") (pinfunction "2_2") (pintype "passive"))
      (node (ref "FB1") (pin "2") (pinfunction "2_2") (pintype "passive"))
      (node (ref "R8") (pin "2") (pinfunction "2_2") (pintype "passive"))
      (node (ref "U2") (pin "1") (pinfunction "IN_1") (pintype "passive"))
    )
    (net (code "110") (name "unconnected-(CN1-ID-Pad4)") (class "Default")
      (node (ref "CN1") (pin "4") (pinfunction "ID_4") (pintype "passive"))
    )
    (net (code "111") (name "unconnected-(CN3-Pad7)") (class "Default")
      (node (ref "CN3") (pin "7") (pinfunction "7_7") (pintype "passive"))
    )
    (net (code "112") (name "unconnected-(U1A-HSYNC_test-PadG6)") (class "Default")
      (node (ref "U1") (pin "G6") (pinfunction "HSYNC_test_G6") (pintype "passive"))
    )
    (net (code "113") (name "unconnected-(U1A-I2S_CLK-PadD1)") (class "Default")
      (node (ref "U1") (pin "D1") (pinfunction "I2S_CLK_D1") (pintype "passive"))
    )
    (net (code "114") (name "unconnected-(U1A-I2S_MCLK-PadC11)") (class "Default")
      (node (ref "U1") (pin "C11") (pinfunction "I2S_MCLK_C11") (pintype "passive"))
    )
    (net (code "115") (name "unconnected-(U1A-I2S_SD-PadD2)") (class "Default")
      (node (ref "U1") (pin "D2") (pinfunction "I2S_SD_D2") (pintype "passive"))
    )
    (net (code "116") (name "unconnected-(U1A-I2S_WS-PadD3)") (class "Default")
      (node (ref "U1") (pin "D3") (pinfunction "I2S_WS_D3") (pintype "passive"))
    )
    (net (code "117") (name "unconnected-(U1A-PCLK_test-PadH8)") (class "Default")
      (node (ref "U1") (pin "H8") (pinfunction "PCLK_test_H8") (pintype "passive"))
    )
    (net (code "118") (name "unconnected-(U1A-UART_CTS-PadE1)") (class "Default")
      (node (ref "U1") (pin "E1") (pinfunction "UART_CTS_E1") (pintype "passive"))
    )
    (net (code "119") (name "unconnected-(U1A-UART_RTS-PadF5)") (class "Default")
      (node (ref "U1") (pin "F5") (pinfunction "UART_RTS_F5") (pintype "passive"))
    )
    (net (code "120") (name "unconnected-(U1A-UART_RX-PadE4)") (class "Default")
      (node (ref "U1") (pin "E4") (pinfunction "UART_RX_E4") (pintype "passive"))
    )
    (net (code "121") (name "unconnected-(U1A-UART_TX-PadE5)") (class "Default")
      (node (ref "U1") (pin "E5") (pinfunction "UART_TX_E5") (pintype "passive"))
    )
    (net (code "122") (name "unconnected-(U1A-VSYNC_test-PadH5)") (class "Default")
      (node (ref "U1") (pin "H5") (pinfunction "VSYNC_test_H5") (pintype "passive"))
    )
    (net (code "123") (name "unconnected-(U5-NC-Pad2)") (class "Default")
      (node (ref "U5") (pin "2") (pinfunction "NC_2") (pintype "passive"))
    )
    (net (code "124") (name "unconnected-(U5-NC-Pad3)") (class "Default")
      (node (ref "U5") (pin "3") (pinfunction "NC_3") (pintype "passive"))
    )
    (net (code "125") (name "unconnected-(U5-NC-Pad4)") (class "Default")
      (node (ref "U5") (pin "4") (pinfunction "NC_4") (pintype "passive"))
    )
    (net (code "126") (name "unconnected-(U5-NC-Pad13)") (class "Default")
      (node (ref "U5") (pin "13") (pinfunction "NC_13") (pintype "passive"))
    )
    (net (code "127") (name "unconnected-(U5-NC-Pad14)") (class "Default")
      (node (ref "U5") (pin "14") (pinfunction "NC_14") (pintype "passive"))
    )
    (net (code "128") (name "unconnected-(U5-NC-Pad17)") (class "Default")
      (node (ref "U5") (pin "17") (pinfunction "NC_17") (pintype "passive"))
    )
    (net (code "129") (name "unconnected-(U7-NC-Pad2)") (class "Default")
      (node (ref "U7") (pin "2") (pinfunction "NC_2") (pintype "passive"))
    )
    (net (code "130") (name "unconnected-(U7-NC-Pad3)") (class "Default")
      (node (ref "U7") (pin "3") (pinfunction "NC_3") (pintype "passive"))
    )
    (net (code "131") (name "unconnected-(U7-NC-Pad4)") (class "Default")
      (node (ref "U7") (pin "4") (pinfunction "NC_4") (pintype "passive"))
    )
    (net (code "132") (name "unconnected-(U7-NC-Pad13)") (class "Default")
      (node (ref "U7") (pin "13") (pinfunction "NC_13") (pintype "passive"))
    )
    (net (code "133") (name "unconnected-(U7-NC-Pad14)") (class "Default")
      (node (ref "U7") (pin "14") (pinfunction "NC_14") (pintype "passive"))
    )
    (net (code "134") (name "unconnected-(U7-NC-Pad17)") (class "Default")
      (node (ref "U7") (pin "17") (pinfunction "NC_17") (pintype "passive"))
    )
    (net (code "135") (name "unconnected-(U8-NC-Pad2)") (class "Default")
      (node (ref "U8") (pin "2") (pinfunction "NC_2") (pintype "passive"))
    )
    (net (code "136") (name "unconnected-(U8-NC-Pad3)") (class "Default")
      (node (ref "U8") (pin "3") (pinfunction "NC_3") (pintype "passive"))
    )
    (net (code "137") (name "unconnected-(U8-NC-Pad4)") (class "Default")
      (node (ref "U8") (pin "4") (pinfunction "NC_4") (pintype "passive"))
    )
    (net (code "138") (name "unconnected-(U8-NC-Pad13)") (class "Default")
      (node (ref "U8") (pin "13") (pinfunction "NC_13") (pintype "passive"))
    )
    (net (code "139") (name "unconnected-(U8-NC-Pad14)") (class "Default")
      (node (ref "U8") (pin "14") (pinfunction "NC_14") (pintype "passive"))
    )
    (net (code "140") (name "unconnected-(U8-NC-Pad17)") (class "Default")
      (node (ref "U8") (pin "17") (pinfunction "NC_17") (pintype "passive"))
    )
    (net (code "141") (name "unconnected-(U8-SS-Pad15)") (class "Default")
      (node (ref "U8") (pin "15") (pinfunction "SS_15") (pintype "passive"))
    )
    (net (code "142") (name "unconnected-(Y1-NC-Pad1)") (class "Default")
      (node (ref "Y1") (pin "1") (pinfunction "NC_1") (pintype "passive"))
    )
  )
)
